# ASIC_1.net
KiCad netlist of a schematic drawn in Altium Designer
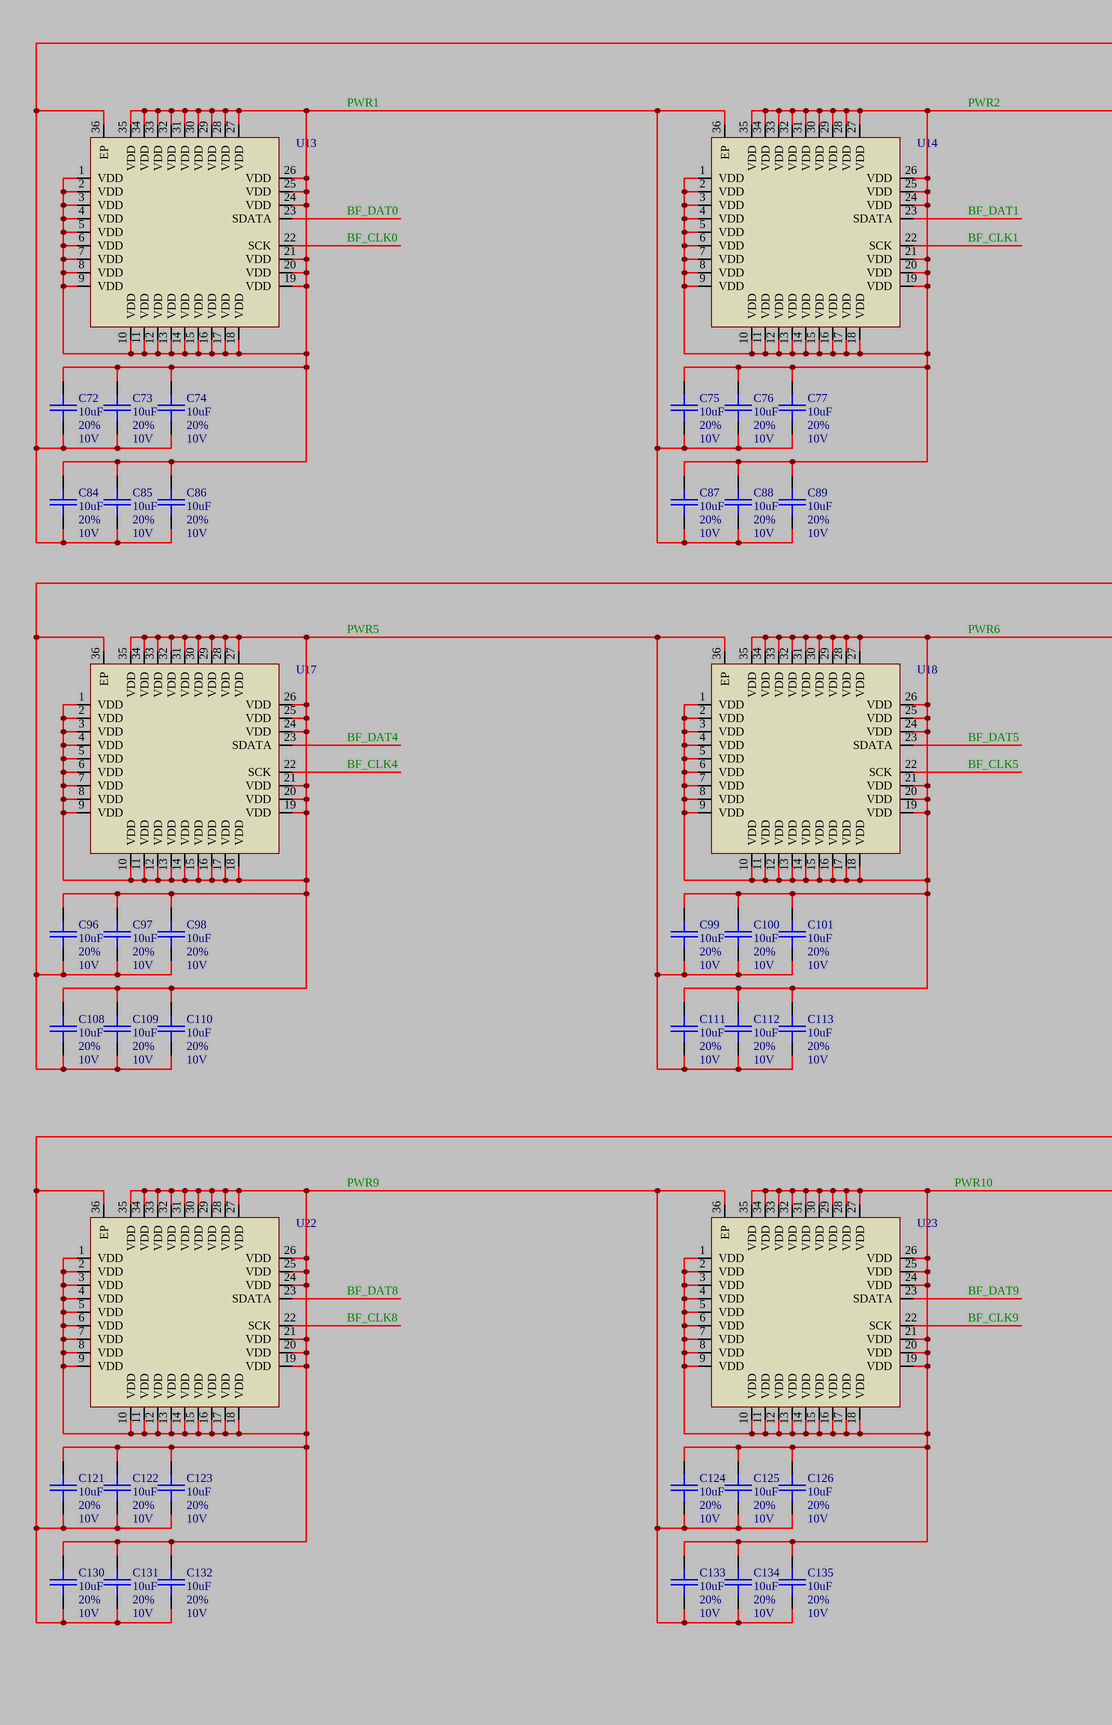
[diagram p0: ASIC_1.SchDoc, left]
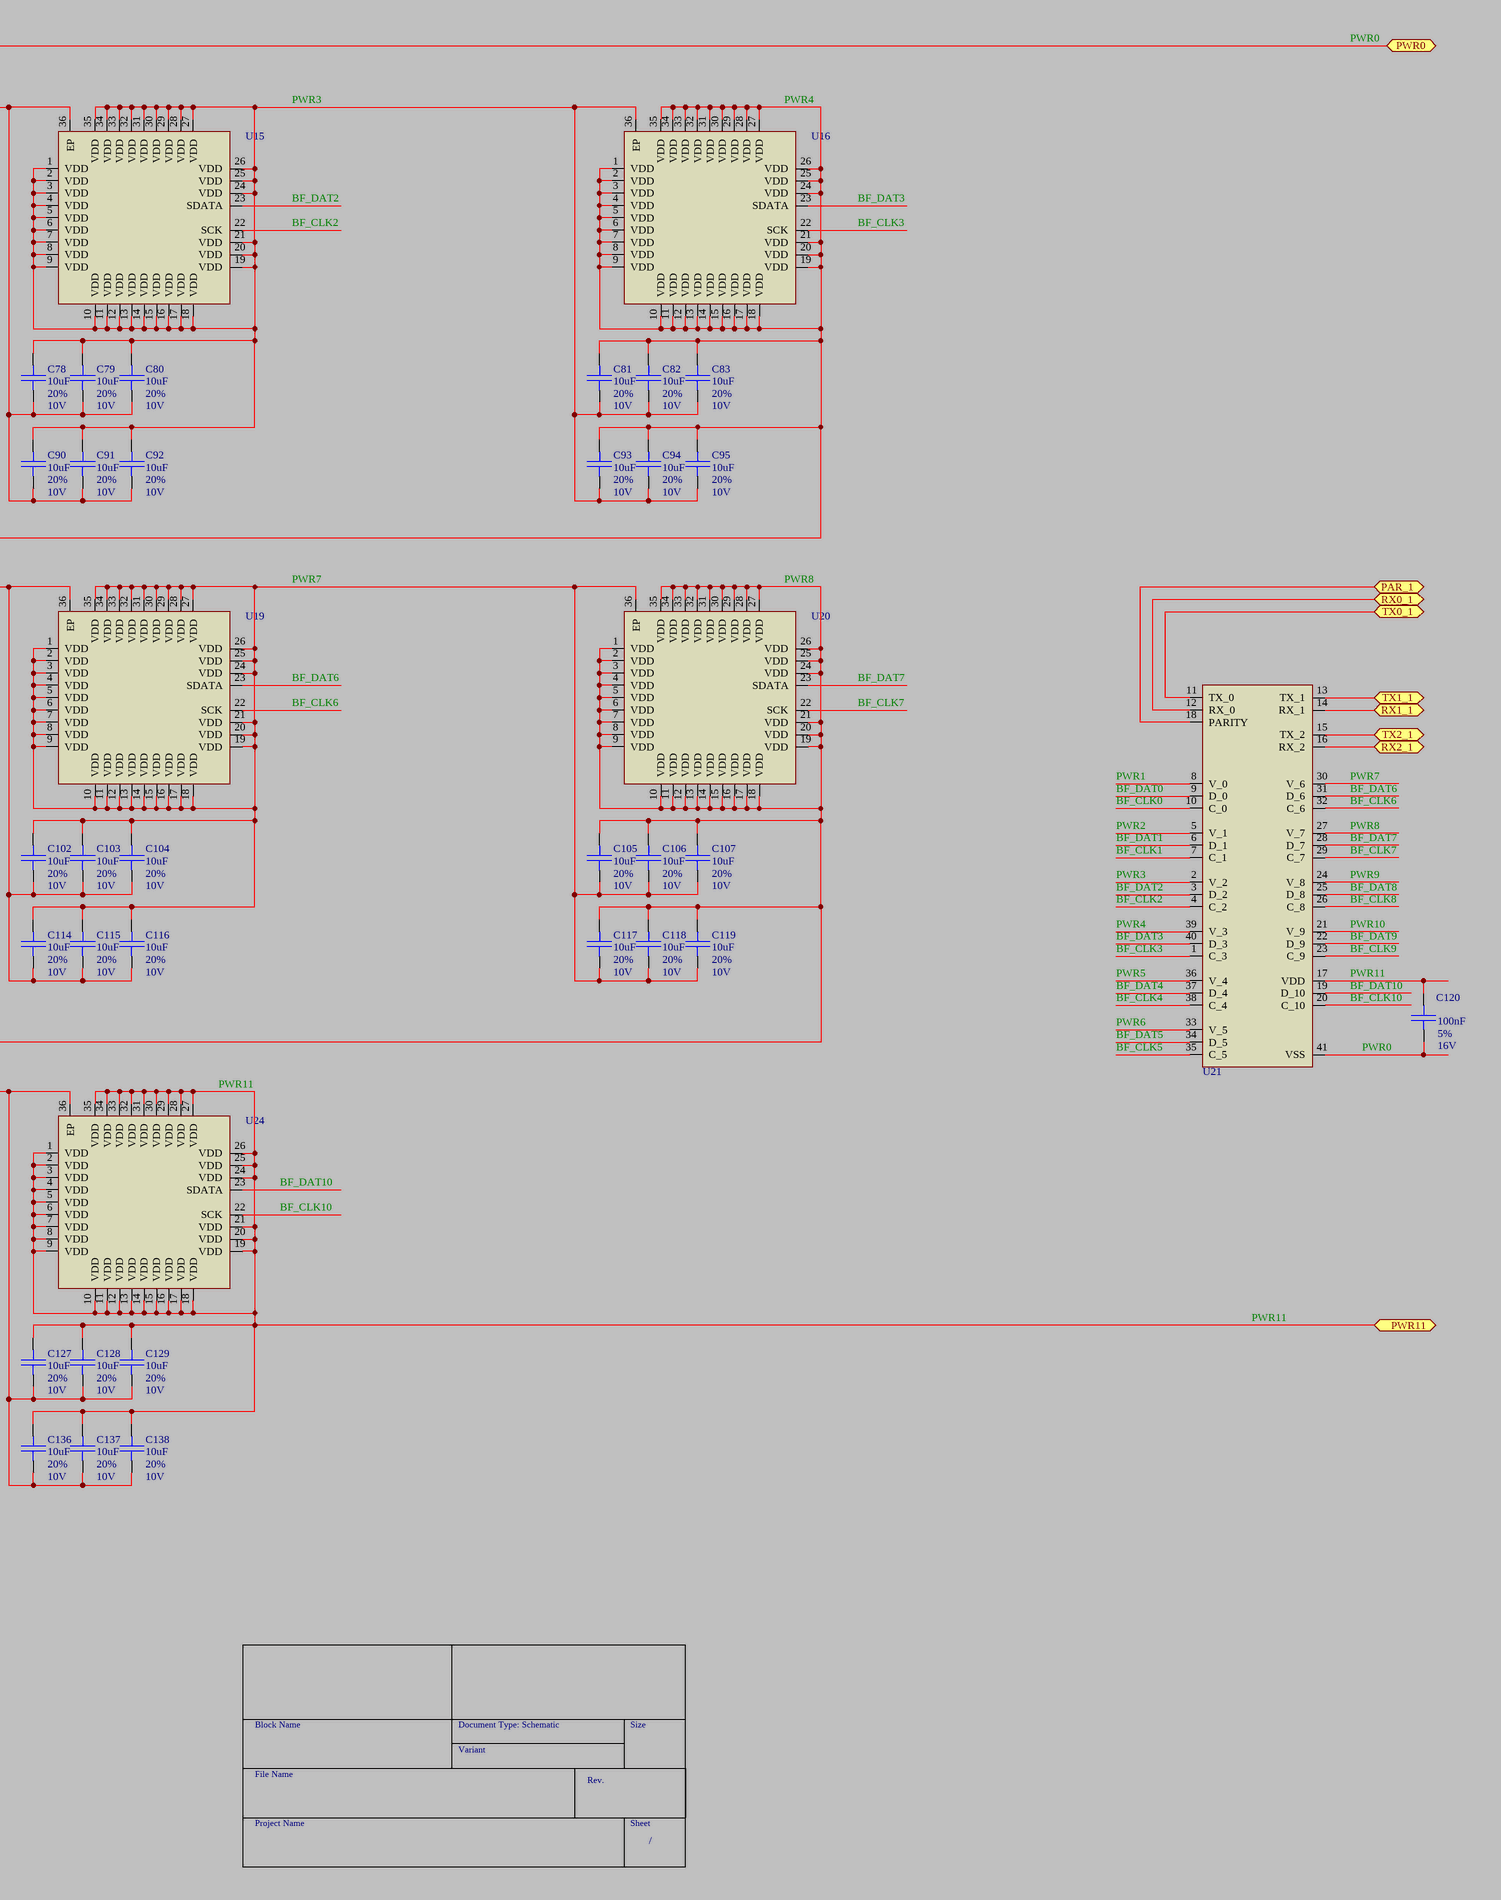
[diagram p1: ASIC_1.SchDoc, right]

(export (version "E")
  (design (tool "Eeschema 10.0.6"))
  (components
    (comp (ref "C72")
      (value "C")
      (footprint "SMD_0402_CAPC1005X70N")
      (fields
        (field (name "DB_PART_NUMBER") "CAP000047481")
        (field (name "DB_VALUE") "10uF")
        (field (name "DB_TOLERANCE") "20%")
        (field (name "DB_VOLTAGE") "10V")
        (field (name "DB_MANUFACTURER_PART") "SAMSUNG    CL05A106MP5NUNC")
        (field (name "DB_APPROVED_BY") "VSN")
      )
      (libsource (lib "Database_Libs1") (part "C"))
    )
    (comp (ref "C73")
      (value "C")
      (footprint "SMD_0402_CAPC1005X70N")
      (fields
        (field (name "DB_PART_NUMBER") "CAP000047481")
        (field (name "DB_VALUE") "10uF")
        (field (name "DB_TOLERANCE") "20%")
        (field (name "DB_VOLTAGE") "10V")
        (field (name "DB_MANUFACTURER_PART") "SAMSUNG    CL05A106MP5NUNC")
        (field (name "DB_APPROVED_BY") "VSN")
      )
      (libsource (lib "Database_Libs1") (part "C"))
    )
    (comp (ref "C74")
      (value "C")
      (footprint "SMD_0402_CAPC1005X70N")
      (fields
        (field (name "DB_PART_NUMBER") "CAP000047481")
        (field (name "DB_VALUE") "10uF")
        (field (name "DB_TOLERANCE") "20%")
        (field (name "DB_VOLTAGE") "10V")
        (field (name "DB_MANUFACTURER_PART") "SAMSUNG    CL05A106MP5NUNC")
        (field (name "DB_APPROVED_BY") "VSN")
      )
      (libsource (lib "Database_Libs1") (part "C"))
    )
    (comp (ref "C75")
      (value "C")
      (footprint "SMD_0402_CAPC1005X70N")
      (fields
        (field (name "DB_PART_NUMBER") "CAP000047481")
        (field (name "DB_VALUE") "10uF")
        (field (name "DB_TOLERANCE") "20%")
        (field (name "DB_VOLTAGE") "10V")
        (field (name "DB_MANUFACTURER_PART") "SAMSUNG    CL05A106MP5NUNC")
        (field (name "DB_APPROVED_BY") "VSN")
      )
      (libsource (lib "Database_Libs1") (part "C"))
    )
    (comp (ref "C76")
      (value "C")
      (footprint "SMD_0402_CAPC1005X70N")
      (fields
        (field (name "DB_PART_NUMBER") "CAP000047481")
        (field (name "DB_VALUE") "10uF")
        (field (name "DB_TOLERANCE") "20%")
        (field (name "DB_VOLTAGE") "10V")
        (field (name "DB_MANUFACTURER_PART") "SAMSUNG    CL05A106MP5NUNC")
        (field (name "DB_APPROVED_BY") "VSN")
      )
      (libsource (lib "Database_Libs1") (part "C"))
    )
    (comp (ref "C77")
      (value "C")
      (footprint "SMD_0402_CAPC1005X70N")
      (fields
        (field (name "DB_PART_NUMBER") "CAP000047481")
        (field (name "DB_VALUE") "10uF")
        (field (name "DB_TOLERANCE") "20%")
        (field (name "DB_VOLTAGE") "10V")
        (field (name "DB_MANUFACTURER_PART") "SAMSUNG    CL05A106MP5NUNC")
        (field (name "DB_APPROVED_BY") "VSN")
      )
      (libsource (lib "Database_Libs1") (part "C"))
    )
    (comp (ref "C78")
      (value "C")
      (footprint "SMD_0402_CAPC1005X70N")
      (fields
        (field (name "DB_PART_NUMBER") "CAP000047481")
        (field (name "DB_VALUE") "10uF")
        (field (name "DB_TOLERANCE") "20%")
        (field (name "DB_VOLTAGE") "10V")
        (field (name "DB_MANUFACTURER_PART") "SAMSUNG    CL05A106MP5NUNC")
        (field (name "DB_APPROVED_BY") "VSN")
      )
      (libsource (lib "Database_Libs1") (part "C"))
    )
    (comp (ref "C79")
      (value "C")
      (footprint "SMD_0402_CAPC1005X70N")
      (fields
        (field (name "DB_PART_NUMBER") "CAP000047481")
        (field (name "DB_VALUE") "10uF")
        (field (name "DB_TOLERANCE") "20%")
        (field (name "DB_VOLTAGE") "10V")
        (field (name "DB_MANUFACTURER_PART") "SAMSUNG    CL05A106MP5NUNC")
        (field (name "DB_APPROVED_BY") "VSN")
      )
      (libsource (lib "Database_Libs1") (part "C"))
    )
    (comp (ref "C80")
      (value "C")
      (footprint "SMD_0402_CAPC1005X70N")
      (fields
        (field (name "DB_PART_NUMBER") "CAP000047481")
        (field (name "DB_VALUE") "10uF")
        (field (name "DB_TOLERANCE") "20%")
        (field (name "DB_VOLTAGE") "10V")
        (field (name "DB_MANUFACTURER_PART") "SAMSUNG    CL05A106MP5NUNC")
        (field (name "DB_APPROVED_BY") "VSN")
      )
      (libsource (lib "Database_Libs1") (part "C"))
    )
    (comp (ref "C81")
      (value "C")
      (footprint "SMD_0402_CAPC1005X70N")
      (fields
        (field (name "DB_PART_NUMBER") "CAP000047481")
        (field (name "DB_VALUE") "10uF")
        (field (name "DB_TOLERANCE") "20%")
        (field (name "DB_VOLTAGE") "10V")
        (field (name "DB_MANUFACTURER_PART") "SAMSUNG    CL05A106MP5NUNC")
        (field (name "DB_APPROVED_BY") "VSN")
      )
      (libsource (lib "Database_Libs1") (part "C"))
    )
    (comp (ref "C82")
      (value "C")
      (footprint "SMD_0402_CAPC1005X70N")
      (fields
        (field (name "DB_PART_NUMBER") "CAP000047481")
        (field (name "DB_VALUE") "10uF")
        (field (name "DB_TOLERANCE") "20%")
        (field (name "DB_VOLTAGE") "10V")
        (field (name "DB_MANUFACTURER_PART") "SAMSUNG    CL05A106MP5NUNC")
        (field (name "DB_APPROVED_BY") "VSN")
      )
      (libsource (lib "Database_Libs1") (part "C"))
    )
    (comp (ref "C83")
      (value "C")
      (footprint "SMD_0402_CAPC1005X70N")
      (fields
        (field (name "DB_PART_NUMBER") "CAP000047481")
        (field (name "DB_VALUE") "10uF")
        (field (name "DB_TOLERANCE") "20%")
        (field (name "DB_VOLTAGE") "10V")
        (field (name "DB_MANUFACTURER_PART") "SAMSUNG    CL05A106MP5NUNC")
        (field (name "DB_APPROVED_BY") "VSN")
      )
      (libsource (lib "Database_Libs1") (part "C"))
    )
    (comp (ref "C84")
      (value "C")
      (footprint "SMD_0402_CAPC1005X70N")
      (fields
        (field (name "DB_PART_NUMBER") "CAP000047481")
        (field (name "DB_VALUE") "10uF")
        (field (name "DB_TOLERANCE") "20%")
        (field (name "DB_VOLTAGE") "10V")
        (field (name "DB_MANUFACTURER_PART") "SAMSUNG    CL05A106MP5NUNC")
        (field (name "DB_APPROVED_BY") "VSN")
      )
      (libsource (lib "Database_Libs1") (part "C"))
    )
    (comp (ref "C85")
      (value "C")
      (footprint "SMD_0402_CAPC1005X70N")
      (fields
        (field (name "DB_PART_NUMBER") "CAP000047481")
        (field (name "DB_VALUE") "10uF")
        (field (name "DB_TOLERANCE") "20%")
        (field (name "DB_VOLTAGE") "10V")
        (field (name "DB_MANUFACTURER_PART") "SAMSUNG    CL05A106MP5NUNC")
        (field (name "DB_APPROVED_BY") "VSN")
      )
      (libsource (lib "Database_Libs1") (part "C"))
    )
    (comp (ref "C86")
      (value "C")
      (footprint "SMD_0402_CAPC1005X70N")
      (fields
        (field (name "DB_PART_NUMBER") "CAP000047481")
        (field (name "DB_VALUE") "10uF")
        (field (name "DB_TOLERANCE") "20%")
        (field (name "DB_VOLTAGE") "10V")
        (field (name "DB_MANUFACTURER_PART") "SAMSUNG    CL05A106MP5NUNC")
        (field (name "DB_APPROVED_BY") "VSN")
      )
      (libsource (lib "Database_Libs1") (part "C"))
    )
    (comp (ref "C87")
      (value "C")
      (footprint "SMD_0402_CAPC1005X70N")
      (fields
        (field (name "DB_PART_NUMBER") "CAP000047481")
        (field (name "DB_VALUE") "10uF")
        (field (name "DB_TOLERANCE") "20%")
        (field (name "DB_VOLTAGE") "10V")
        (field (name "DB_MANUFACTURER_PART") "SAMSUNG    CL05A106MP5NUNC")
        (field (name "DB_APPROVED_BY") "VSN")
      )
      (libsource (lib "Database_Libs1") (part "C"))
    )
    (comp (ref "C88")
      (value "C")
      (footprint "SMD_0402_CAPC1005X70N")
      (fields
        (field (name "DB_PART_NUMBER") "CAP000047481")
        (field (name "DB_VALUE") "10uF")
        (field (name "DB_TOLERANCE") "20%")
        (field (name "DB_VOLTAGE") "10V")
        (field (name "DB_MANUFACTURER_PART") "SAMSUNG    CL05A106MP5NUNC")
        (field (name "DB_APPROVED_BY") "VSN")
      )
      (libsource (lib "Database_Libs1") (part "C"))
    )
    (comp (ref "C89")
      (value "C")
      (footprint "SMD_0402_CAPC1005X70N")
      (fields
        (field (name "DB_PART_NUMBER") "CAP000047481")
        (field (name "DB_VALUE") "10uF")
        (field (name "DB_TOLERANCE") "20%")
        (field (name "DB_VOLTAGE") "10V")
        (field (name "DB_MANUFACTURER_PART") "SAMSUNG    CL05A106MP5NUNC")
        (field (name "DB_APPROVED_BY") "VSN")
      )
      (libsource (lib "Database_Libs1") (part "C"))
    )
    (comp (ref "C90")
      (value "C")
      (footprint "SMD_0402_CAPC1005X70N")
      (fields
        (field (name "DB_PART_NUMBER") "CAP000047481")
        (field (name "DB_VALUE") "10uF")
        (field (name "DB_TOLERANCE") "20%")
        (field (name "DB_VOLTAGE") "10V")
        (field (name "DB_MANUFACTURER_PART") "SAMSUNG    CL05A106MP5NUNC")
        (field (name "DB_APPROVED_BY") "VSN")
      )
      (libsource (lib "Database_Libs1") (part "C"))
    )
    (comp (ref "C91")
      (value "C")
      (footprint "SMD_0402_CAPC1005X70N")
      (fields
        (field (name "DB_PART_NUMBER") "CAP000047481")
        (field (name "DB_VALUE") "10uF")
        (field (name "DB_TOLERANCE") "20%")
        (field (name "DB_VOLTAGE") "10V")
        (field (name "DB_MANUFACTURER_PART") "SAMSUNG    CL05A106MP5NUNC")
        (field (name "DB_APPROVED_BY") "VSN")
      )
      (libsource (lib "Database_Libs1") (part "C"))
    )
    (comp (ref "C92")
      (value "C")
      (footprint "SMD_0402_CAPC1005X70N")
      (fields
        (field (name "DB_PART_NUMBER") "CAP000047481")
        (field (name "DB_VALUE") "10uF")
        (field (name "DB_TOLERANCE") "20%")
        (field (name "DB_VOLTAGE") "10V")
        (field (name "DB_MANUFACTURER_PART") "SAMSUNG    CL05A106MP5NUNC")
        (field (name "DB_APPROVED_BY") "VSN")
      )
      (libsource (lib "Database_Libs1") (part "C"))
    )
    (comp (ref "C93")
      (value "C")
      (footprint "SMD_0402_CAPC1005X70N")
      (fields
        (field (name "DB_PART_NUMBER") "CAP000047481")
        (field (name "DB_VALUE") "10uF")
        (field (name "DB_TOLERANCE") "20%")
        (field (name "DB_VOLTAGE") "10V")
        (field (name "DB_MANUFACTURER_PART") "SAMSUNG    CL05A106MP5NUNC")
        (field (name "DB_APPROVED_BY") "VSN")
      )
      (libsource (lib "Database_Libs1") (part "C"))
    )
    (comp (ref "C94")
      (value "C")
      (footprint "SMD_0402_CAPC1005X70N")
      (fields
        (field (name "DB_PART_NUMBER") "CAP000047481")
        (field (name "DB_VALUE") "10uF")
        (field (name "DB_TOLERANCE") "20%")
        (field (name "DB_VOLTAGE") "10V")
        (field (name "DB_MANUFACTURER_PART") "SAMSUNG    CL05A106MP5NUNC")
        (field (name "DB_APPROVED_BY") "VSN")
      )
      (libsource (lib "Database_Libs1") (part "C"))
    )
    (comp (ref "C95")
      (value "C")
      (footprint "SMD_0402_CAPC1005X70N")
      (fields
        (field (name "DB_PART_NUMBER") "CAP000047481")
        (field (name "DB_VALUE") "10uF")
        (field (name "DB_TOLERANCE") "20%")
        (field (name "DB_VOLTAGE") "10V")
        (field (name "DB_MANUFACTURER_PART") "SAMSUNG    CL05A106MP5NUNC")
        (field (name "DB_APPROVED_BY") "VSN")
      )
      (libsource (lib "Database_Libs1") (part "C"))
    )
    (comp (ref "C96")
      (value "C")
      (footprint "SMD_0402_CAPC1005X70N")
      (fields
        (field (name "DB_PART_NUMBER") "CAP000047481")
        (field (name "DB_VALUE") "10uF")
        (field (name "DB_TOLERANCE") "20%")
        (field (name "DB_VOLTAGE") "10V")
        (field (name "DB_MANUFACTURER_PART") "SAMSUNG    CL05A106MP5NUNC")
        (field (name "DB_APPROVED_BY") "VSN")
      )
      (libsource (lib "Database_Libs1") (part "C"))
    )
    (comp (ref "C97")
      (value "C")
      (footprint "SMD_0402_CAPC1005X70N")
      (fields
        (field (name "DB_PART_NUMBER") "CAP000047481")
        (field (name "DB_VALUE") "10uF")
        (field (name "DB_TOLERANCE") "20%")
        (field (name "DB_VOLTAGE") "10V")
        (field (name "DB_MANUFACTURER_PART") "SAMSUNG    CL05A106MP5NUNC")
        (field (name "DB_APPROVED_BY") "VSN")
      )
      (libsource (lib "Database_Libs1") (part "C"))
    )
    (comp (ref "C98")
      (value "C")
      (footprint "SMD_0402_CAPC1005X70N")
      (fields
        (field (name "DB_PART_NUMBER") "CAP000047481")
        (field (name "DB_VALUE") "10uF")
        (field (name "DB_TOLERANCE") "20%")
        (field (name "DB_VOLTAGE") "10V")
        (field (name "DB_MANUFACTURER_PART") "SAMSUNG    CL05A106MP5NUNC")
        (field (name "DB_APPROVED_BY") "VSN")
      )
      (libsource (lib "Database_Libs1") (part "C"))
    )
    (comp (ref "C99")
      (value "C")
      (footprint "SMD_0402_CAPC1005X70N")
      (fields
        (field (name "DB_PART_NUMBER") "CAP000047481")
        (field (name "DB_VALUE") "10uF")
        (field (name "DB_TOLERANCE") "20%")
        (field (name "DB_VOLTAGE") "10V")
        (field (name "DB_MANUFACTURER_PART") "SAMSUNG    CL05A106MP5NUNC")
        (field (name "DB_APPROVED_BY") "VSN")
      )
      (libsource (lib "Database_Libs1") (part "C"))
    )
    (comp (ref "C100")
      (value "C")
      (footprint "SMD_0402_CAPC1005X70N")
      (fields
        (field (name "DB_PART_NUMBER") "CAP000047481")
        (field (name "DB_VALUE") "10uF")
        (field (name "DB_TOLERANCE") "20%")
        (field (name "DB_VOLTAGE") "10V")
        (field (name "DB_MANUFACTURER_PART") "SAMSUNG    CL05A106MP5NUNC")
        (field (name "DB_APPROVED_BY") "VSN")
      )
      (libsource (lib "Database_Libs1") (part "C"))
    )
    (comp (ref "C101")
      (value "C")
      (footprint "SMD_0402_CAPC1005X70N")
      (fields
        (field (name "DB_PART_NUMBER") "CAP000047481")
        (field (name "DB_VALUE") "10uF")
        (field (name "DB_TOLERANCE") "20%")
        (field (name "DB_VOLTAGE") "10V")
        (field (name "DB_MANUFACTURER_PART") "SAMSUNG    CL05A106MP5NUNC")
        (field (name "DB_APPROVED_BY") "VSN")
      )
      (libsource (lib "Database_Libs1") (part "C"))
    )
    (comp (ref "C102")
      (value "C")
      (footprint "SMD_0402_CAPC1005X70N")
      (fields
        (field (name "DB_PART_NUMBER") "CAP000047481")
        (field (name "DB_VALUE") "10uF")
        (field (name "DB_TOLERANCE") "20%")
        (field (name "DB_VOLTAGE") "10V")
        (field (name "DB_MANUFACTURER_PART") "SAMSUNG    CL05A106MP5NUNC")
        (field (name "DB_APPROVED_BY") "VSN")
      )
      (libsource (lib "Database_Libs1") (part "C"))
    )
    (comp (ref "C103")
      (value "C")
      (footprint "SMD_0402_CAPC1005X70N")
      (fields
        (field (name "DB_PART_NUMBER") "CAP000047481")
        (field (name "DB_VALUE") "10uF")
        (field (name "DB_TOLERANCE") "20%")
        (field (name "DB_VOLTAGE") "10V")
        (field (name "DB_MANUFACTURER_PART") "SAMSUNG    CL05A106MP5NUNC")
        (field (name "DB_APPROVED_BY") "VSN")
      )
      (libsource (lib "Database_Libs1") (part "C"))
    )
    (comp (ref "C104")
      (value "C")
      (footprint "SMD_0402_CAPC1005X70N")
      (fields
        (field (name "DB_PART_NUMBER") "CAP000047481")
        (field (name "DB_VALUE") "10uF")
        (field (name "DB_TOLERANCE") "20%")
        (field (name "DB_VOLTAGE") "10V")
        (field (name "DB_MANUFACTURER_PART") "SAMSUNG    CL05A106MP5NUNC")
        (field (name "DB_APPROVED_BY") "VSN")
      )
      (libsource (lib "Database_Libs1") (part "C"))
    )
    (comp (ref "C105")
      (value "C")
      (footprint "SMD_0402_CAPC1005X70N")
      (fields
        (field (name "DB_PART_NUMBER") "CAP000047481")
        (field (name "DB_VALUE") "10uF")
        (field (name "DB_TOLERANCE") "20%")
        (field (name "DB_VOLTAGE") "10V")
        (field (name "DB_MANUFACTURER_PART") "SAMSUNG    CL05A106MP5NUNC")
        (field (name "DB_APPROVED_BY") "VSN")
      )
      (libsource (lib "Database_Libs1") (part "C"))
    )
    (comp (ref "C106")
      (value "C")
      (footprint "SMD_0402_CAPC1005X70N")
      (fields
        (field (name "DB_PART_NUMBER") "CAP000047481")
        (field (name "DB_VALUE") "10uF")
        (field (name "DB_TOLERANCE") "20%")
        (field (name "DB_VOLTAGE") "10V")
        (field (name "DB_MANUFACTURER_PART") "SAMSUNG    CL05A106MP5NUNC")
        (field (name "DB_APPROVED_BY") "VSN")
      )
      (libsource (lib "Database_Libs1") (part "C"))
    )
    (comp (ref "C107")
      (value "C")
      (footprint "SMD_0402_CAPC1005X70N")
      (fields
        (field (name "DB_PART_NUMBER") "CAP000047481")
        (field (name "DB_VALUE") "10uF")
        (field (name "DB_TOLERANCE") "20%")
        (field (name "DB_VOLTAGE") "10V")
        (field (name "DB_MANUFACTURER_PART") "SAMSUNG    CL05A106MP5NUNC")
        (field (name "DB_APPROVED_BY") "VSN")
      )
      (libsource (lib "Database_Libs1") (part "C"))
    )
    (comp (ref "C108")
      (value "C")
      (footprint "SMD_0402_CAPC1005X70N")
      (fields
        (field (name "DB_PART_NUMBER") "CAP000047481")
        (field (name "DB_VALUE") "10uF")
        (field (name "DB_TOLERANCE") "20%")
        (field (name "DB_VOLTAGE") "10V")
        (field (name "DB_MANUFACTURER_PART") "SAMSUNG    CL05A106MP5NUNC")
        (field (name "DB_APPROVED_BY") "VSN")
      )
      (libsource (lib "Database_Libs1") (part "C"))
    )
    (comp (ref "C109")
      (value "C")
      (footprint "SMD_0402_CAPC1005X70N")
      (fields
        (field (name "DB_PART_NUMBER") "CAP000047481")
        (field (name "DB_VALUE") "10uF")
        (field (name "DB_TOLERANCE") "20%")
        (field (name "DB_VOLTAGE") "10V")
        (field (name "DB_MANUFACTURER_PART") "SAMSUNG    CL05A106MP5NUNC")
        (field (name "DB_APPROVED_BY") "VSN")
      )
      (libsource (lib "Database_Libs1") (part "C"))
    )
    (comp (ref "C110")
      (value "C")
      (footprint "SMD_0402_CAPC1005X70N")
      (fields
        (field (name "DB_PART_NUMBER") "CAP000047481")
        (field (name "DB_VALUE") "10uF")
        (field (name "DB_TOLERANCE") "20%")
        (field (name "DB_VOLTAGE") "10V")
        (field (name "DB_MANUFACTURER_PART") "SAMSUNG    CL05A106MP5NUNC")
        (field (name "DB_APPROVED_BY") "VSN")
      )
      (libsource (lib "Database_Libs1") (part "C"))
    )
    (comp (ref "C111")
      (value "C")
      (footprint "SMD_0402_CAPC1005X70N")
      (fields
        (field (name "DB_PART_NUMBER") "CAP000047481")
        (field (name "DB_VALUE") "10uF")
        (field (name "DB_TOLERANCE") "20%")
        (field (name "DB_VOLTAGE") "10V")
        (field (name "DB_MANUFACTURER_PART") "SAMSUNG    CL05A106MP5NUNC")
        (field (name "DB_APPROVED_BY") "VSN")
      )
      (libsource (lib "Database_Libs1") (part "C"))
    )
    (comp (ref "C112")
      (value "C")
      (footprint "SMD_0402_CAPC1005X70N")
      (fields
        (field (name "DB_PART_NUMBER") "CAP000047481")
        (field (name "DB_VALUE") "10uF")
        (field (name "DB_TOLERANCE") "20%")
        (field (name "DB_VOLTAGE") "10V")
        (field (name "DB_MANUFACTURER_PART") "SAMSUNG    CL05A106MP5NUNC")
        (field (name "DB_APPROVED_BY") "VSN")
      )
      (libsource (lib "Database_Libs1") (part "C"))
    )
    (comp (ref "C113")
      (value "C")
      (footprint "SMD_0402_CAPC1005X70N")
      (fields
        (field (name "DB_PART_NUMBER") "CAP000047481")
        (field (name "DB_VALUE") "10uF")
        (field (name "DB_TOLERANCE") "20%")
        (field (name "DB_VOLTAGE") "10V")
        (field (name "DB_MANUFACTURER_PART") "SAMSUNG    CL05A106MP5NUNC")
        (field (name "DB_APPROVED_BY") "VSN")
      )
      (libsource (lib "Database_Libs1") (part "C"))
    )
    (comp (ref "C114")
      (value "C")
      (footprint "SMD_0402_CAPC1005X70N")
      (fields
        (field (name "DB_PART_NUMBER") "CAP000047481")
        (field (name "DB_VALUE") "10uF")
        (field (name "DB_TOLERANCE") "20%")
        (field (name "DB_VOLTAGE") "10V")
        (field (name "DB_MANUFACTURER_PART") "SAMSUNG    CL05A106MP5NUNC")
        (field (name "DB_APPROVED_BY") "VSN")
      )
      (libsource (lib "Database_Libs1") (part "C"))
    )
    (comp (ref "C115")
      (value "C")
      (footprint "SMD_0402_CAPC1005X70N")
      (fields
        (field (name "DB_PART_NUMBER") "CAP000047481")
        (field (name "DB_VALUE") "10uF")
        (field (name "DB_TOLERANCE") "20%")
        (field (name "DB_VOLTAGE") "10V")
        (field (name "DB_MANUFACTURER_PART") "SAMSUNG    CL05A106MP5NUNC")
        (field (name "DB_APPROVED_BY") "VSN")
      )
      (libsource (lib "Database_Libs1") (part "C"))
    )
    (comp (ref "C116")
      (value "C")
      (footprint "SMD_0402_CAPC1005X70N")
      (fields
        (field (name "DB_PART_NUMBER") "CAP000047481")
        (field (name "DB_VALUE") "10uF")
        (field (name "DB_TOLERANCE") "20%")
        (field (name "DB_VOLTAGE") "10V")
        (field (name "DB_MANUFACTURER_PART") "SAMSUNG    CL05A106MP5NUNC")
        (field (name "DB_APPROVED_BY") "VSN")
      )
      (libsource (lib "Database_Libs1") (part "C"))
    )
    (comp (ref "C117")
      (value "C")
      (footprint "SMD_0402_CAPC1005X70N")
      (fields
        (field (name "DB_PART_NUMBER") "CAP000047481")
        (field (name "DB_VALUE") "10uF")
        (field (name "DB_TOLERANCE") "20%")
        (field (name "DB_VOLTAGE") "10V")
        (field (name "DB_MANUFACTURER_PART") "SAMSUNG    CL05A106MP5NUNC")
        (field (name "DB_APPROVED_BY") "VSN")
      )
      (libsource (lib "Database_Libs1") (part "C"))
    )
    (comp (ref "C118")
      (value "C")
      (footprint "SMD_0402_CAPC1005X70N")
      (fields
        (field (name "DB_PART_NUMBER") "CAP000047481")
        (field (name "DB_VALUE") "10uF")
        (field (name "DB_TOLERANCE") "20%")
        (field (name "DB_VOLTAGE") "10V")
        (field (name "DB_MANUFACTURER_PART") "SAMSUNG    CL05A106MP5NUNC")
        (field (name "DB_APPROVED_BY") "VSN")
      )
      (libsource (lib "Database_Libs1") (part "C"))
    )
    (comp (ref "C119")
      (value "C")
      (footprint "SMD_0402_CAPC1005X70N")
      (fields
        (field (name "DB_PART_NUMBER") "CAP000047481")
        (field (name "DB_VALUE") "10uF")
        (field (name "DB_TOLERANCE") "20%")
        (field (name "DB_VOLTAGE") "10V")
        (field (name "DB_MANUFACTURER_PART") "SAMSUNG    CL05A106MP5NUNC")
        (field (name "DB_APPROVED_BY") "VSN")
      )
      (libsource (lib "Database_Libs1") (part "C"))
    )
    (comp (ref "C120")
      (value "C")
      (footprint "SMD_0603_CAPC1608X95N")
      (fields
        (field (name "DB_PART_NUMBER") "CAP000027134")
        (field (name "DB_VALUE") "100nF")
        (field (name "DB_TOLERANCE") "5%")
        (field (name "DB_VOLTAGE") "16V")
        (field (name "DB_MANUFACTURER_PART") "KEMET    C0603C104J4RAC")
      )
      (libsource (lib "Database_Libs1") (part "C"))
    )
    (comp (ref "C121")
      (value "C")
      (footprint "SMD_0402_CAPC1005X70N")
      (fields
        (field (name "DB_PART_NUMBER") "CAP000047481")
        (field (name "DB_VALUE") "10uF")
        (field (name "DB_TOLERANCE") "20%")
        (field (name "DB_VOLTAGE") "10V")
        (field (name "DB_MANUFACTURER_PART") "SAMSUNG    CL05A106MP5NUNC")
        (field (name "DB_APPROVED_BY") "VSN")
      )
      (libsource (lib "Database_Libs1") (part "C"))
    )
    (comp (ref "C122")
      (value "C")
      (footprint "SMD_0402_CAPC1005X70N")
      (fields
        (field (name "DB_PART_NUMBER") "CAP000047481")
        (field (name "DB_VALUE") "10uF")
        (field (name "DB_TOLERANCE") "20%")
        (field (name "DB_VOLTAGE") "10V")
        (field (name "DB_MANUFACTURER_PART") "SAMSUNG    CL05A106MP5NUNC")
        (field (name "DB_APPROVED_BY") "VSN")
      )
      (libsource (lib "Database_Libs1") (part "C"))
    )
    (comp (ref "C123")
      (value "C")
      (footprint "SMD_0402_CAPC1005X70N")
      (fields
        (field (name "DB_PART_NUMBER") "CAP000047481")
        (field (name "DB_VALUE") "10uF")
        (field (name "DB_TOLERANCE") "20%")
        (field (name "DB_VOLTAGE") "10V")
        (field (name "DB_MANUFACTURER_PART") "SAMSUNG    CL05A106MP5NUNC")
        (field (name "DB_APPROVED_BY") "VSN")
      )
      (libsource (lib "Database_Libs1") (part "C"))
    )
    (comp (ref "C124")
      (value "C")
      (footprint "SMD_0402_CAPC1005X70N")
      (fields
        (field (name "DB_PART_NUMBER") "CAP000047481")
        (field (name "DB_VALUE") "10uF")
        (field (name "DB_TOLERANCE") "20%")
        (field (name "DB_VOLTAGE") "10V")
        (field (name "DB_MANUFACTURER_PART") "SAMSUNG    CL05A106MP5NUNC")
        (field (name "DB_APPROVED_BY") "VSN")
      )
      (libsource (lib "Database_Libs1") (part "C"))
    )
    (comp (ref "C125")
      (value "C")
      (footprint "SMD_0402_CAPC1005X70N")
      (fields
        (field (name "DB_PART_NUMBER") "CAP000047481")
        (field (name "DB_VALUE") "10uF")
        (field (name "DB_TOLERANCE") "20%")
        (field (name "DB_VOLTAGE") "10V")
        (field (name "DB_MANUFACTURER_PART") "SAMSUNG    CL05A106MP5NUNC")
        (field (name "DB_APPROVED_BY") "VSN")
      )
      (libsource (lib "Database_Libs1") (part "C"))
    )
    (comp (ref "C126")
      (value "C")
      (footprint "SMD_0402_CAPC1005X70N")
      (fields
        (field (name "DB_PART_NUMBER") "CAP000047481")
        (field (name "DB_VALUE") "10uF")
        (field (name "DB_TOLERANCE") "20%")
        (field (name "DB_VOLTAGE") "10V")
        (field (name "DB_MANUFACTURER_PART") "SAMSUNG    CL05A106MP5NUNC")
        (field (name "DB_APPROVED_BY") "VSN")
      )
      (libsource (lib "Database_Libs1") (part "C"))
    )
    (comp (ref "C127")
      (value "C")
      (footprint "SMD_0402_CAPC1005X70N")
      (fields
        (field (name "DB_PART_NUMBER") "CAP000047481")
        (field (name "DB_VALUE") "10uF")
        (field (name "DB_TOLERANCE") "20%")
        (field (name "DB_VOLTAGE") "10V")
        (field (name "DB_MANUFACTURER_PART") "SAMSUNG    CL05A106MP5NUNC")
        (field (name "DB_APPROVED_BY") "VSN")
      )
      (libsource (lib "Database_Libs1") (part "C"))
    )
    (comp (ref "C128")
      (value "C")
      (footprint "SMD_0402_CAPC1005X70N")
      (fields
        (field (name "DB_PART_NUMBER") "CAP000047481")
        (field (name "DB_VALUE") "10uF")
        (field (name "DB_TOLERANCE") "20%")
        (field (name "DB_VOLTAGE") "10V")
        (field (name "DB_MANUFACTURER_PART") "SAMSUNG    CL05A106MP5NUNC")
        (field (name "DB_APPROVED_BY") "VSN")
      )
      (libsource (lib "Database_Libs1") (part "C"))
    )
    (comp (ref "C129")
      (value "C")
      (footprint "SMD_0402_CAPC1005X70N")
      (fields
        (field (name "DB_PART_NUMBER") "CAP000047481")
        (field (name "DB_VALUE") "10uF")
        (field (name "DB_TOLERANCE") "20%")
        (field (name "DB_VOLTAGE") "10V")
        (field (name "DB_MANUFACTURER_PART") "SAMSUNG    CL05A106MP5NUNC")
        (field (name "DB_APPROVED_BY") "VSN")
      )
      (libsource (lib "Database_Libs1") (part "C"))
    )
    (comp (ref "C130")
      (value "C")
      (footprint "SMD_0402_CAPC1005X70N")
      (fields
        (field (name "DB_PART_NUMBER") "CAP000047481")
        (field (name "DB_VALUE") "10uF")
        (field (name "DB_TOLERANCE") "20%")
        (field (name "DB_VOLTAGE") "10V")
        (field (name "DB_MANUFACTURER_PART") "SAMSUNG    CL05A106MP5NUNC")
        (field (name "DB_APPROVED_BY") "VSN")
      )
      (libsource (lib "Database_Libs1") (part "C"))
    )
    (comp (ref "C131")
      (value "C")
      (footprint "SMD_0402_CAPC1005X70N")
      (fields
        (field (name "DB_PART_NUMBER") "CAP000047481")
        (field (name "DB_VALUE") "10uF")
        (field (name "DB_TOLERANCE") "20%")
        (field (name "DB_VOLTAGE") "10V")
        (field (name "DB_MANUFACTURER_PART") "SAMSUNG    CL05A106MP5NUNC")
        (field (name "DB_APPROVED_BY") "VSN")
      )
      (libsource (lib "Database_Libs1") (part "C"))
    )
    (comp (ref "C132")
      (value "C")
      (footprint "SMD_0402_CAPC1005X70N")
      (fields
        (field (name "DB_PART_NUMBER") "CAP000047481")
        (field (name "DB_VALUE") "10uF")
        (field (name "DB_TOLERANCE") "20%")
        (field (name "DB_VOLTAGE") "10V")
        (field (name "DB_MANUFACTURER_PART") "SAMSUNG    CL05A106MP5NUNC")
        (field (name "DB_APPROVED_BY") "VSN")
      )
      (libsource (lib "Database_Libs1") (part "C"))
    )
    (comp (ref "C133")
      (value "C")
      (footprint "SMD_0402_CAPC1005X70N")
      (fields
        (field (name "DB_PART_NUMBER") "CAP000047481")
        (field (name "DB_VALUE") "10uF")
        (field (name "DB_TOLERANCE") "20%")
        (field (name "DB_VOLTAGE") "10V")
        (field (name "DB_MANUFACTURER_PART") "SAMSUNG    CL05A106MP5NUNC")
        (field (name "DB_APPROVED_BY") "VSN")
      )
      (libsource (lib "Database_Libs1") (part "C"))
    )
    (comp (ref "C134")
      (value "C")
      (footprint "SMD_0402_CAPC1005X70N")
      (fields
        (field (name "DB_PART_NUMBER") "CAP000047481")
        (field (name "DB_VALUE") "10uF")
        (field (name "DB_TOLERANCE") "20%")
        (field (name "DB_VOLTAGE") "10V")
        (field (name "DB_MANUFACTURER_PART") "SAMSUNG    CL05A106MP5NUNC")
        (field (name "DB_APPROVED_BY") "VSN")
      )
      (libsource (lib "Database_Libs1") (part "C"))
    )
    (comp (ref "C135")
      (value "C")
      (footprint "SMD_0402_CAPC1005X70N")
      (fields
        (field (name "DB_PART_NUMBER") "CAP000047481")
        (field (name "DB_VALUE") "10uF")
        (field (name "DB_TOLERANCE") "20%")
        (field (name "DB_VOLTAGE") "10V")
        (field (name "DB_MANUFACTURER_PART") "SAMSUNG    CL05A106MP5NUNC")
        (field (name "DB_APPROVED_BY") "VSN")
      )
      (libsource (lib "Database_Libs1") (part "C"))
    )
    (comp (ref "C136")
      (value "C")
      (footprint "SMD_0402_CAPC1005X70N")
      (fields
        (field (name "DB_PART_NUMBER") "CAP000047481")
        (field (name "DB_VALUE") "10uF")
        (field (name "DB_TOLERANCE") "20%")
        (field (name "DB_VOLTAGE") "10V")
        (field (name "DB_MANUFACTURER_PART") "SAMSUNG    CL05A106MP5NUNC")
        (field (name "DB_APPROVED_BY") "VSN")
      )
      (libsource (lib "Database_Libs1") (part "C"))
    )
    (comp (ref "C137")
      (value "C")
      (footprint "SMD_0402_CAPC1005X70N")
      (fields
        (field (name "DB_PART_NUMBER") "CAP000047481")
        (field (name "DB_VALUE") "10uF")
        (field (name "DB_TOLERANCE") "20%")
        (field (name "DB_VOLTAGE") "10V")
        (field (name "DB_MANUFACTURER_PART") "SAMSUNG    CL05A106MP5NUNC")
        (field (name "DB_APPROVED_BY") "VSN")
      )
      (libsource (lib "Database_Libs1") (part "C"))
    )
    (comp (ref "C138")
      (value "C")
      (footprint "SMD_0402_CAPC1005X70N")
      (fields
        (field (name "DB_PART_NUMBER") "CAP000047481")
        (field (name "DB_VALUE") "10uF")
        (field (name "DB_TOLERANCE") "20%")
        (field (name "DB_VOLTAGE") "10V")
        (field (name "DB_MANUFACTURER_PART") "SAMSUNG    CL05A106MP5NUNC")
        (field (name "DB_APPROVED_BY") "VSN")
      )
      (libsource (lib "Database_Libs1") (part "C"))
    )
    (comp (ref "U13")
      (value "IC_BITFURY16")
      (footprint "SMD_QFN50P600X600X175-36AN")
      (description "BitFury 2016 16 nm")
      (libsource (lib "BitCoin") (part "IC_BITFURY16"))
    )
    (comp (ref "U14")
      (value "IC_BITFURY16")
      (footprint "SMD_QFN50P600X600X175-36AN")
      (description "BitFury 2016 16 nm")
      (libsource (lib "BitCoin") (part "IC_BITFURY16"))
    )
    (comp (ref "U15")
      (value "IC_BITFURY16")
      (footprint "SMD_QFN50P600X600X175-36AN")
      (description "BitFury 2016 16 nm")
      (libsource (lib "BitCoin") (part "IC_BITFURY16"))
    )
    (comp (ref "U16")
      (value "IC_BITFURY16")
      (footprint "SMD_QFN50P600X600X175-36AN")
      (description "BitFury 2016 16 nm")
      (libsource (lib "BitCoin") (part "IC_BITFURY16"))
    )
    (comp (ref "U17")
      (value "IC_BITFURY16")
      (footprint "SMD_QFN50P600X600X175-36AN")
      (description "BitFury 2016 16 nm")
      (libsource (lib "BitCoin") (part "IC_BITFURY16"))
    )
    (comp (ref "U18")
      (value "IC_BITFURY16")
      (footprint "SMD_QFN50P600X600X175-36AN")
      (description "BitFury 2016 16 nm")
      (libsource (lib "BitCoin") (part "IC_BITFURY16"))
    )
    (comp (ref "U19")
      (value "IC_BITFURY16")
      (footprint "SMD_QFN50P600X600X175-36AN")
      (description "BitFury 2016 16 nm")
      (libsource (lib "BitCoin") (part "IC_BITFURY16"))
    )
    (comp (ref "U20")
      (value "IC_BITFURY16")
      (footprint "SMD_QFN50P600X600X175-36AN")
      (description "BitFury 2016 16 nm")
      (libsource (lib "BitCoin") (part "IC_BITFURY16"))
    )
    (comp (ref "U21")
      (value "IC_BTC250")
      (footprint "SMD_QFN40P500X500X80-41N")
      (fields (field (name "DB_MANUFACTURER_PART") "BTC250 QFN40 EP"))
      (libsource (lib "BitCoin") (part "IC_BTC250"))
    )
    (comp (ref "U22")
      (value "IC_BITFURY16")
      (footprint "SMD_QFN50P600X600X175-36AN")
      (description "BitFury 2016 16 nm")
      (libsource (lib "BitCoin") (part "IC_BITFURY16"))
    )
    (comp (ref "U23")
      (value "IC_BITFURY16")
      (footprint "SMD_QFN50P600X600X175-36AN")
      (description "BitFury 2016 16 nm")
      (libsource (lib "BitCoin") (part "IC_BITFURY16"))
    )
    (comp (ref "U24")
      (value "IC_BITFURY16")
      (footprint "SMD_QFN50P600X600X175-36AN")
      (description "BitFury 2016 16 nm")
      (libsource (lib "BitCoin") (part "IC_BITFURY16"))
    )
  )
  (nets
    (net (code "1") (name "/BF_CLK0") (class "Default")
      (node (ref "U13") (pin "22") (pinfunction "SCK_22") (pintype "passive"))
      (node (ref "U21") (pin "10") (pinfunction "C_0_10") (pintype "passive"))
    )
    (net (code "2") (name "/BF_CLK1") (class "Default")
      (node (ref "U14") (pin "22") (pinfunction "SCK_22") (pintype "passive"))
      (node (ref "U21") (pin "7") (pinfunction "C_1_7") (pintype "passive"))
    )
    (net (code "3") (name "/BF_CLK2") (class "Default")
      (node (ref "U15") (pin "22") (pinfunction "SCK_22") (pintype "passive"))
      (node (ref "U21") (pin "4") (pinfunction "C_2_4") (pintype "passive"))
    )
    (net (code "4") (name "/BF_CLK3") (class "Default")
      (node (ref "U16") (pin "22") (pinfunction "SCK_22") (pintype "passive"))
      (node (ref "U21") (pin "1") (pinfunction "C_3_1") (pintype "passive"))
    )
    (net (code "5") (name "/BF_CLK4") (class "Default")
      (node (ref "U17") (pin "22") (pinfunction "SCK_22") (pintype "passive"))
      (node (ref "U21") (pin "38") (pinfunction "C_4_38") (pintype "passive"))
    )
    (net (code "6") (name "/BF_CLK5") (class "Default")
      (node (ref "U18") (pin "22") (pinfunction "SCK_22") (pintype "passive"))
      (node (ref "U21") (pin "35") (pinfunction "C_5_35") (pintype "passive"))
    )
    (net (code "7") (name "/BF_CLK6") (class "Default")
      (node (ref "U19") (pin "22") (pinfunction "SCK_22") (pintype "passive"))
      (node (ref "U21") (pin "32") (pinfunction "C_6_32") (pintype "passive"))
    )
    (net (code "8") (name "/BF_CLK7") (class "Default")
      (node (ref "U20") (pin "22") (pinfunction "SCK_22") (pintype "passive"))
      (node (ref "U21") (pin "29") (pinfunction "C_7_29") (pintype "passive"))
    )
    (net (code "9") (name "/BF_CLK8") (class "Default")
      (node (ref "U21") (pin "26") (pinfunction "C_8_26") (pintype "passive"))
      (node (ref "U22") (pin "22") (pinfunction "SCK_22") (pintype "passive"))
    )
    (net (code "10") (name "/BF_CLK9") (class "Default")
      (node (ref "U21") (pin "23") (pinfunction "C_9_23") (pintype "passive"))
      (node (ref "U23") (pin "22") (pinfunction "SCK_22") (pintype "passive"))
    )
    (net (code "11") (name "/BF_CLK10") (class "Default")
      (node (ref "U21") (pin "20") (pinfunction "C_10_20") (pintype "passive"))
      (node (ref "U24") (pin "22") (pinfunction "SCK_22") (pintype "passive"))
    )
    (net (code "12") (name "/BF_DAT0") (class "Default")
      (node (ref "U13") (pin "23") (pinfunction "SDATA_23") (pintype "passive"))
      (node (ref "U21") (pin "9") (pinfunction "D_0_9") (pintype "passive"))
    )
    (net (code "13") (name "/BF_DAT1") (class "Default")
      (node (ref "U14") (pin "23") (pinfunction "SDATA_23") (pintype "passive"))
      (node (ref "U21") (pin "6") (pinfunction "D_1_6") (pintype "passive"))
    )
    (net (code "14") (name "/BF_DAT2") (class "Default")
      (node (ref "U15") (pin "23") (pinfunction "SDATA_23") (pintype "passive"))
      (node (ref "U21") (pin "3") (pinfunction "D_2_3") (pintype "passive"))
    )
    (net (code "15") (name "/BF_DAT3") (class "Default")
      (node (ref "U16") (pin "23") (pinfunction "SDATA_23") (pintype "passive"))
      (node (ref "U21") (pin "40") (pinfunction "D_3_40") (pintype "passive"))
    )
    (net (code "16") (name "/BF_DAT4") (class "Default")
      (node (ref "U17") (pin "23") (pinfunction "SDATA_23") (pintype "passive"))
      (node (ref "U21") (pin "37") (pinfunction "D_4_37") (pintype "passive"))
    )
    (net (code "17") (name "/BF_DAT5") (class "Default")
      (node (ref "U18") (pin "23") (pinfunction "SDATA_23") (pintype "passive"))
      (node (ref "U21") (pin "34") (pinfunction "D_5_34") (pintype "passive"))
    )
    (net (code "18") (name "/BF_DAT6") (class "Default")
      (node (ref "U19") (pin "23") (pinfunction "SDATA_23") (pintype "passive"))
      (node (ref "U21") (pin "31") (pinfunction "D_6_31") (pintype "passive"))
    )
    (net (code "19") (name "/BF_DAT7") (class "Default")
      (node (ref "U20") (pin "23") (pinfunction "SDATA_23") (pintype "passive"))
      (node (ref "U21") (pin "28") (pinfunction "D_7_28") (pintype "passive"))
    )
    (net (code "20") (name "/BF_DAT8") (class "Default")
      (node (ref "U21") (pin "25") (pinfunction "D_8_25") (pintype "passive"))
      (node (ref "U22") (pin "23") (pinfunction "SDATA_23") (pintype "passive"))
    )
    (net (code "21") (name "/BF_DAT9") (class "Default")
      (node (ref "U21") (pin "22") (pinfunction "D_9_22") (pintype "passive"))
      (node (ref "U23") (pin "23") (pinfunction "SDATA_23") (pintype "passive"))
    )
    (net (code "22") (name "/BF_DAT10") (class "Default")
      (node (ref "U21") (pin "19") (pinfunction "D_10_19") (pintype "passive"))
      (node (ref "U24") (pin "23") (pinfunction "SDATA_23") (pintype "passive"))
    )
    (net (code "23") (name "/PAR_1") (class "Default")
      (node (ref "U21") (pin "18") (pinfunction "PARITY_18") (pintype "passive"))
    )
    (net (code "24") (name "/PWR0") (class "Default")
      (node (ref "C120") (pin "2") (pinfunction "2_2") (pintype "passive"))
      (node (ref "C72") (pin "2") (pinfunction "2_2") (pintype "passive"))
      (node (ref "C73") (pin "2") (pinfunction "2_2") (pintype "passive"))
      (node (ref "C74") (pin "2") (pinfunction "2_2") (pintype "passive"))
      (node (ref "C84") (pin "2") (pinfunction "2_2") (pintype "passive"))
      (node (ref "C85") (pin "2") (pinfunction "2_2") (pintype "passive"))
      (node (ref "C86") (pin "2") (pinfunction "2_2") (pintype "passive"))
      (node (ref "U13") (pin "36") (pinfunction "EP_36") (pintype "passive"))
      (node (ref "U21") (pin "41") (pinfunction "VSS_41") (pintype "passive"))
    )
    (net (code "25") (name "/PWR1") (class "Default")
      (node (ref "C72") (pin "1") (pinfunction "1_1") (pintype "passive"))
      (node (ref "C73") (pin "1") (pinfunction "1_1") (pintype "passive"))
      (node (ref "C74") (pin "1") (pinfunction "1_1") (pintype "passive"))
      (node (ref "C75") (pin "2") (pinfunction "2_2") (pintype "passive"))
      (node (ref "C76") (pin "2") (pinfunction "2_2") (pintype "passive"))
      (node (ref "C77") (pin "2") (pinfunction "2_2") (pintype "passive"))
      (node (ref "C84") (pin "1") (pinfunction "1_1") (pintype "passive"))
      (node (ref "C85") (pin "1") (pinfunction "1_1") (pintype "passive"))
      (node (ref "C86") (pin "1") (pinfunction "1_1") (pintype "passive"))
      (node (ref "C87") (pin "2") (pinfunction "2_2") (pintype "passive"))
      (node (ref "C88") (pin "2") (pinfunction "2_2") (pintype "passive"))
      (node (ref "C89") (pin "2") (pinfunction "2_2") (pintype "passive"))
      (node (ref "U13") (pin "1") (pinfunction "VDD_1") (pintype "passive"))
      (node (ref "U13") (pin "10") (pinfunction "VDD_10") (pintype "passive"))
      (node (ref "U13") (pin "11") (pinfunction "VDD_11") (pintype "passive"))
      (node (ref "U13") (pin "12") (pinfunction "VDD_12") (pintype "passive"))
      (node (ref "U13") (pin "13") (pinfunction "VDD_13") (pintype "passive"))
      (node (ref "U13") (pin "14") (pinfunction "VDD_14") (pintype "passive"))
      (node (ref "U13") (pin "15") (pinfunction "VDD_15") (pintype "passive"))
      (node (ref "U13") (pin "16") (pinfunction "VDD_16") (pintype "passive"))
      (node (ref "U13") (pin "17") (pinfunction "VDD_17") (pintype "passive"))
      (node (ref "U13") (pin "18") (pinfunction "VDD_18") (pintype "passive"))
      (node (ref "U13") (pin "19") (pinfunction "VDD_19") (pintype "passive"))
      (node (ref "U13") (pin "2") (pinfunction "VDD_2") (pintype "passive"))
      (node (ref "U13") (pin "20") (pinfunction "VDD_20") (pintype "passive"))
      (node (ref "U13") (pin "21") (pinfunction "VDD_21") (pintype "passive"))
      (node (ref "U13") (pin "24") (pinfunction "VDD_24") (pintype "passive"))
      (node (ref "U13") (pin "25") (pinfunction "VDD_25") (pintype "passive"))
      (node (ref "U13") (pin "26") (pinfunction "VDD_26") (pintype "passive"))
      (node (ref "U13") (pin "27") (pinfunction "VDD_27") (pintype "passive"))
      (node (ref "U13") (pin "28") (pinfunction "VDD_28") (pintype "passive"))
      (node (ref "U13") (pin "29") (pinfunction "VDD_29") (pintype "passive"))
      (node (ref "U13") (pin "3") (pinfunction "VDD_3") (pintype "passive"))
      (node (ref "U13") (pin "30") (pinfunction "VDD_30") (pintype "passive"))
      (node (ref "U13") (pin "31") (pinfunction "VDD_31") (pintype "passive"))
      (node (ref "U13") (pin "32") (pinfunction "VDD_32") (pintype "passive"))
      (node (ref "U13") (pin "33") (pinfunction "VDD_33") (pintype "passive"))
      (node (ref "U13") (pin "34") (pinfunction "VDD_34") (pintype "passive"))
      (node (ref "U13") (pin "35") (pinfunction "VDD_35") (pintype "passive"))
      (node (ref "U13") (pin "4") (pinfunction "VDD_4") (pintype "passive"))
      (node (ref "U13") (pin "5") (pinfunction "VDD_5") (pintype "passive"))
      (node (ref "U13") (pin "6") (pinfunction "VDD_6") (pintype "passive"))
      (node (ref "U13") (pin "7") (pinfunction "VDD_7") (pintype "passive"))
      (node (ref "U13") (pin "8") (pinfunction "VDD_8") (pintype "passive"))
      (node (ref "U13") (pin "9") (pinfunction "VDD_9") (pintype "passive"))
      (node (ref "U14") (pin "36") (pinfunction "EP_36") (pintype "passive"))
      (node (ref "U21") (pin "8") (pinfunction "V_0_8") (pintype "passive"))
    )
    (net (code "26") (name "/PWR2") (class "Default")
      (node (ref "C75") (pin "1") (pinfunction "1_1") (pintype "passive"))
      (node (ref "C76") (pin "1") (pinfunction "1_1") (pintype "passive"))
      (node (ref "C77") (pin "1") (pinfunction "1_1") (pintype "passive"))
      (node (ref "C78") (pin "2") (pinfunction "2_2") (pintype "passive"))
      (node (ref "C79") (pin "2") (pinfunction "2_2") (pintype "passive"))
      (node (ref "C80") (pin "2") (pinfunction "2_2") (pintype "passive"))
      (node (ref "C87") (pin "1") (pinfunction "1_1") (pintype "passive"))
      (node (ref "C88") (pin "1") (pinfunction "1_1") (pintype "passive"))
      (node (ref "C89") (pin "1") (pinfunction "1_1") (pintype "passive"))
      (node (ref "C90") (pin "2") (pinfunction "2_2") (pintype "passive"))
      (node (ref "C91") (pin "2") (pinfunction "2_2") (pintype "passive"))
      (node (ref "C92") (pin "2") (pinfunction "2_2") (pintype "passive"))
      (node (ref "U14") (pin "1") (pinfunction "VDD_1") (pintype "passive"))
      (node (ref "U14") (pin "10") (pinfunction "VDD_10") (pintype "passive"))
      (node (ref "U14") (pin "11") (pinfunction "VDD_11") (pintype "passive"))
      (node (ref "U14") (pin "12") (pinfunction "VDD_12") (pintype "passive"))
      (node (ref "U14") (pin "13") (pinfunction "VDD_13") (pintype "passive"))
      (node (ref "U14") (pin "14") (pinfunction "VDD_14") (pintype "passive"))
      (node (ref "U14") (pin "15") (pinfunction "VDD_15") (pintype "passive"))
      (node (ref "U14") (pin "16") (pinfunction "VDD_16") (pintype "passive"))
      (node (ref "U14") (pin "17") (pinfunction "VDD_17") (pintype "passive"))
      (node (ref "U14") (pin "18") (pinfunction "VDD_18") (pintype "passive"))
      (node (ref "U14") (pin "19") (pinfunction "VDD_19") (pintype "passive"))
      (node (ref "U14") (pin "2") (pinfunction "VDD_2") (pintype "passive"))
      (node (ref "U14") (pin "20") (pinfunction "VDD_20") (pintype "passive"))
      (node (ref "U14") (pin "21") (pinfunction "VDD_21") (pintype "passive"))
      (node (ref "U14") (pin "24") (pinfunction "VDD_24") (pintype "passive"))
      (node (ref "U14") (pin "25") (pinfunction "VDD_25") (pintype "passive"))
      (node (ref "U14") (pin "26") (pinfunction "VDD_26") (pintype "passive"))
      (node (ref "U14") (pin "27") (pinfunction "VDD_27") (pintype "passive"))
      (node (ref "U14") (pin "28") (pinfunction "VDD_28") (pintype "passive"))
      (node (ref "U14") (pin "29") (pinfunction "VDD_29") (pintype "passive"))
      (node (ref "U14") (pin "3") (pinfunction "VDD_3") (pintype "passive"))
      (node (ref "U14") (pin "30") (pinfunction "VDD_30") (pintype "passive"))
      (node (ref "U14") (pin "31") (pinfunction "VDD_31") (pintype "passive"))
      (node (ref "U14") (pin "32") (pinfunction "VDD_32") (pintype "passive"))
      (node (ref "U14") (pin "33") (pinfunction "VDD_33") (pintype "passive"))
      (node (ref "U14") (pin "34") (pinfunction "VDD_34") (pintype "passive"))
      (node (ref "U14") (pin "35") (pinfunction "VDD_35") (pintype "passive"))
      (node (ref "U14") (pin "4") (pinfunction "VDD_4") (pintype "passive"))
      (node (ref "U14") (pin "5") (pinfunction "VDD_5") (pintype "passive"))
      (node (ref "U14") (pin "6") (pinfunction "VDD_6") (pintype "passive"))
      (node (ref "U14") (pin "7") (pinfunction "VDD_7") (pintype "passive"))
      (node (ref "U14") (pin "8") (pinfunction "VDD_8") (pintype "passive"))
      (node (ref "U14") (pin "9") (pinfunction "VDD_9") (pintype "passive"))
      (node (ref "U15") (pin "36") (pinfunction "EP_36") (pintype "passive"))
      (node (ref "U21") (pin "5") (pinfunction "V_1_5") (pintype "passive"))
    )
    (net (code "27") (name "/PWR3") (class "Default")
      (node (ref "C78") (pin "1") (pinfunction "1_1") (pintype "passive"))
      (node (ref "C79") (pin "1") (pinfunction "1_1") (pintype "passive"))
      (node (ref "C80") (pin "1") (pinfunction "1_1") (pintype "passive"))
      (node (ref "C81") (pin "2") (pinfunction "2_2") (pintype "passive"))
      (node (ref "C82") (pin "2") (pinfunction "2_2") (pintype "passive"))
      (node (ref "C83") (pin "2") (pinfunction "2_2") (pintype "passive"))
      (node (ref "C90") (pin "1") (pinfunction "1_1") (pintype "passive"))
      (node (ref "C91") (pin "1") (pinfunction "1_1") (pintype "passive"))
      (node (ref "C92") (pin "1") (pinfunction "1_1") (pintype "passive"))
      (node (ref "C93") (pin "2") (pinfunction "2_2") (pintype "passive"))
      (node (ref "C94") (pin "2") (pinfunction "2_2") (pintype "passive"))
      (node (ref "C95") (pin "2") (pinfunction "2_2") (pintype "passive"))
      (node (ref "U15") (pin "1") (pinfunction "VDD_1") (pintype "passive"))
      (node (ref "U15") (pin "10") (pinfunction "VDD_10") (pintype "passive"))
      (node (ref "U15") (pin "11") (pinfunction "VDD_11") (pintype "passive"))
      (node (ref "U15") (pin "12") (pinfunction "VDD_12") (pintype "passive"))
      (node (ref "U15") (pin "13") (pinfunction "VDD_13") (pintype "passive"))
      (node (ref "U15") (pin "14") (pinfunction "VDD_14") (pintype "passive"))
      (node (ref "U15") (pin "15") (pinfunction "VDD_15") (pintype "passive"))
      (node (ref "U15") (pin "16") (pinfunction "VDD_16") (pintype "passive"))
      (node (ref "U15") (pin "17") (pinfunction "VDD_17") (pintype "passive"))
      (node (ref "U15") (pin "18") (pinfunction "VDD_18") (pintype "passive"))
      (node (ref "U15") (pin "19") (pinfunction "VDD_19") (pintype "passive"))
      (node (ref "U15") (pin "2") (pinfunction "VDD_2") (pintype "passive"))
      (node (ref "U15") (pin "20") (pinfunction "VDD_20") (pintype "passive"))
      (node (ref "U15") (pin "21") (pinfunction "VDD_21") (pintype "passive"))
      (node (ref "U15") (pin "24") (pinfunction "VDD_24") (pintype "passive"))
      (node (ref "U15") (pin "25") (pinfunction "VDD_25") (pintype "passive"))
      (node (ref "U15") (pin "26") (pinfunction "VDD_26") (pintype "passive"))
      (node (ref "U15") (pin "27") (pinfunction "VDD_27") (pintype "passive"))
      (node (ref "U15") (pin "28") (pinfunction "VDD_28") (pintype "passive"))
      (node (ref "U15") (pin "29") (pinfunction "VDD_29") (pintype "passive"))
      (node (ref "U15") (pin "3") (pinfunction "VDD_3") (pintype "passive"))
      (node (ref "U15") (pin "30") (pinfunction "VDD_30") (pintype "passive"))
      (node (ref "U15") (pin "31") (pinfunction "VDD_31") (pintype "passive"))
      (node (ref "U15") (pin "32") (pinfunction "VDD_32") (pintype "passive"))
      (node (ref "U15") (pin "33") (pinfunction "VDD_33") (pintype "passive"))
      (node (ref "U15") (pin "34") (pinfunction "VDD_34") (pintype "passive"))
      (node (ref "U15") (pin "35") (pinfunction "VDD_35") (pintype "passive"))
      (node (ref "U15") (pin "4") (pinfunction "VDD_4") (pintype "passive"))
      (node (ref "U15") (pin "5") (pinfunction "VDD_5") (pintype "passive"))
      (node (ref "U15") (pin "6") (pinfunction "VDD_6") (pintype "passive"))
      (node (ref "U15") (pin "7") (pinfunction "VDD_7") (pintype "passive"))
      (node (ref "U15") (pin "8") (pinfunction "VDD_8") (pintype "passive"))
      (node (ref "U15") (pin "9") (pinfunction "VDD_9") (pintype "passive"))
      (node (ref "U16") (pin "36") (pinfunction "EP_36") (pintype "passive"))
      (node (ref "U21") (pin "2") (pinfunction "V_2_2") (pintype "passive"))
    )
    (net (code "28") (name "/PWR4") (class "Default")
      (node (ref "C108") (pin "2") (pinfunction "2_2") (pintype "passive"))
      (node (ref "C109") (pin "2") (pinfunction "2_2") (pintype "passive"))
      (node (ref "C110") (pin "2") (pinfunction "2_2") (pintype "passive"))
      (node (ref "C81") (pin "1") (pinfunction "1_1") (pintype "passive"))
      (node (ref "C82") (pin "1") (pinfunction "1_1") (pintype "passive"))
      (node (ref "C83") (pin "1") (pinfunction "1_1") (pintype "passive"))
      (node (ref "C93") (pin "1") (pinfunction "1_1") (pintype "passive"))
      (node (ref "C94") (pin "1") (pinfunction "1_1") (pintype "passive"))
      (node (ref "C95") (pin "1") (pinfunction "1_1") (pintype "passive"))
      (node (ref "C96") (pin "2") (pinfunction "2_2") (pintype "passive"))
      (node (ref "C97") (pin "2") (pinfunction "2_2") (pintype "passive"))
      (node (ref "C98") (pin "2") (pinfunction "2_2") (pintype "passive"))
      (node (ref "U16") (pin "1") (pinfunction "VDD_1") (pintype "passive"))
      (node (ref "U16") (pin "10") (pinfunction "VDD_10") (pintype "passive"))
      (node (ref "U16") (pin "11") (pinfunction "VDD_11") (pintype "passive"))
      (node (ref "U16") (pin "12") (pinfunction "VDD_12") (pintype "passive"))
      (node (ref "U16") (pin "13") (pinfunction "VDD_13") (pintype "passive"))
      (node (ref "U16") (pin "14") (pinfunction "VDD_14") (pintype "passive"))
      (node (ref "U16") (pin "15") (pinfunction "VDD_15") (pintype "passive"))
      (node (ref "U16") (pin "16") (pinfunction "VDD_16") (pintype "passive"))
      (node (ref "U16") (pin "17") (pinfunction "VDD_17") (pintype "passive"))
      (node (ref "U16") (pin "18") (pinfunction "VDD_18") (pintype "passive"))
      (node (ref "U16") (pin "19") (pinfunction "VDD_19") (pintype "passive"))
      (node (ref "U16") (pin "2") (pinfunction "VDD_2") (pintype "passive"))
      (node (ref "U16") (pin "20") (pinfunction "VDD_20") (pintype "passive"))
      (node (ref "U16") (pin "21") (pinfunction "VDD_21") (pintype "passive"))
      (node (ref "U16") (pin "24") (pinfunction "VDD_24") (pintype "passive"))
      (node (ref "U16") (pin "25") (pinfunction "VDD_25") (pintype "passive"))
      (node (ref "U16") (pin "26") (pinfunction "VDD_26") (pintype "passive"))
      (node (ref "U16") (pin "27") (pinfunction "VDD_27") (pintype "passive"))
      (node (ref "U16") (pin "28") (pinfunction "VDD_28") (pintype "passive"))
      (node (ref "U16") (pin "29") (pinfunction "VDD_29") (pintype "passive"))
      (node (ref "U16") (pin "3") (pinfunction "VDD_3") (pintype "passive"))
      (node (ref "U16") (pin "30") (pinfunction "VDD_30") (pintype "passive"))
      (node (ref "U16") (pin "31") (pinfunction "VDD_31") (pintype "passive"))
      (node (ref "U16") (pin "32") (pinfunction "VDD_32") (pintype "passive"))
      (node (ref "U16") (pin "33") (pinfunction "VDD_33") (pintype "passive"))
      (node (ref "U16") (pin "34") (pinfunction "VDD_34") (pintype "passive"))
      (node (ref "U16") (pin "35") (pinfunction "VDD_35") (pintype "passive"))
      (node (ref "U16") (pin "4") (pinfunction "VDD_4") (pintype "passive"))
      (node (ref "U16") (pin "5") (pinfunction "VDD_5") (pintype "passive"))
      (node (ref "U16") (pin "6") (pinfunction "VDD_6") (pintype "passive"))
      (node (ref "U16") (pin "7") (pinfunction "VDD_7") (pintype "passive"))
      (node (ref "U16") (pin "8") (pinfunction "VDD_8") (pintype "passive"))
      (node (ref "U16") (pin "9") (pinfunction "VDD_9") (pintype "passive"))
      (node (ref "U17") (pin "36") (pinfunction "EP_36") (pintype "passive"))
      (node (ref "U21") (pin "39") (pinfunction "V_3_39") (pintype "passive"))
    )
    (net (code "29") (name "/PWR5") (class "Default")
      (node (ref "C100") (pin "2") (pinfunction "2_2") (pintype "passive"))
      (node (ref "C101") (pin "2") (pinfunction "2_2") (pintype "passive"))
      (node (ref "C108") (pin "1") (pinfunction "1_1") (pintype "passive"))
      (node (ref "C109") (pin "1") (pinfunction "1_1") (pintype "passive"))
      (node (ref "C110") (pin "1") (pinfunction "1_1") (pintype "passive"))
      (node (ref "C111") (pin "2") (pinfunction "2_2") (pintype "passive"))
      (node (ref "C112") (pin "2") (pinfunction "2_2") (pintype "passive"))
      (node (ref "C113") (pin "2") (pinfunction "2_2") (pintype "passive"))
      (node (ref "C96") (pin "1") (pinfunction "1_1") (pintype "passive"))
      (node (ref "C97") (pin "1") (pinfunction "1_1") (pintype "passive"))
      (node (ref "C98") (pin "1") (pinfunction "1_1") (pintype "passive"))
      (node (ref "C99") (pin "2") (pinfunction "2_2") (pintype "passive"))
      (node (ref "U17") (pin "1") (pinfunction "VDD_1") (pintype "passive"))
      (node (ref "U17") (pin "10") (pinfunction "VDD_10") (pintype "passive"))
      (node (ref "U17") (pin "11") (pinfunction "VDD_11") (pintype "passive"))
      (node (ref "U17") (pin "12") (pinfunction "VDD_12") (pintype "passive"))
      (node (ref "U17") (pin "13") (pinfunction "VDD_13") (pintype "passive"))
      (node (ref "U17") (pin "14") (pinfunction "VDD_14") (pintype "passive"))
      (node (ref "U17") (pin "15") (pinfunction "VDD_15") (pintype "passive"))
      (node (ref "U17") (pin "16") (pinfunction "VDD_16") (pintype "passive"))
      (node (ref "U17") (pin "17") (pinfunction "VDD_17") (pintype "passive"))
      (node (ref "U17") (pin "18") (pinfunction "VDD_18") (pintype "passive"))
      (node (ref "U17") (pin "19") (pinfunction "VDD_19") (pintype "passive"))
      (node (ref "U17") (pin "2") (pinfunction "VDD_2") (pintype "passive"))
      (node (ref "U17") (pin "20") (pinfunction "VDD_20") (pintype "passive"))
      (node (ref "U17") (pin "21") (pinfunction "VDD_21") (pintype "passive"))
      (node (ref "U17") (pin "24") (pinfunction "VDD_24") (pintype "passive"))
      (node (ref "U17") (pin "25") (pinfunction "VDD_25") (pintype "passive"))
      (node (ref "U17") (pin "26") (pinfunction "VDD_26") (pintype "passive"))
      (node (ref "U17") (pin "27") (pinfunction "VDD_27") (pintype "passive"))
      (node (ref "U17") (pin "28") (pinfunction "VDD_28") (pintype "passive"))
      (node (ref "U17") (pin "29") (pinfunction "VDD_29") (pintype "passive"))
      (node (ref "U17") (pin "3") (pinfunction "VDD_3") (pintype "passive"))
      (node (ref "U17") (pin "30") (pinfunction "VDD_30") (pintype "passive"))
      (node (ref "U17") (pin "31") (pinfunction "VDD_31") (pintype "passive"))
      (node (ref "U17") (pin "32") (pinfunction "VDD_32") (pintype "passive"))
      (node (ref "U17") (pin "33") (pinfunction "VDD_33") (pintype "passive"))
      (node (ref "U17") (pin "34") (pinfunction "VDD_34") (pintype "passive"))
      (node (ref "U17") (pin "35") (pinfunction "VDD_35") (pintype "passive"))
      (node (ref "U17") (pin "4") (pinfunction "VDD_4") (pintype "passive"))
      (node (ref "U17") (pin "5") (pinfunction "VDD_5") (pintype "passive"))
      (node (ref "U17") (pin "6") (pinfunction "VDD_6") (pintype "passive"))
      (node (ref "U17") (pin "7") (pinfunction "VDD_7") (pintype "passive"))
      (node (ref "U17") (pin "8") (pinfunction "VDD_8") (pintype "passive"))
      (node (ref "U17") (pin "9") (pinfunction "VDD_9") (pintype "passive"))
      (node (ref "U18") (pin "36") (pinfunction "EP_36") (pintype "passive"))
      (node (ref "U21") (pin "36") (pinfunction "V_4_36") (pintype "passive"))
    )
    (net (code "30") (name "/PWR6") (class "Default")
      (node (ref "C100") (pin "1") (pinfunction "1_1") (pintype "passive"))
      (node (ref "C101") (pin "1") (pinfunction "1_1") (pintype "passive"))
      (node (ref "C102") (pin "2") (pinfunction "2_2") (pintype "passive"))
      (node (ref "C103") (pin "2") (pinfunction "2_2") (pintype "passive"))
      (node (ref "C104") (pin "2") (pinfunction "2_2") (pintype "passive"))
      (node (ref "C111") (pin "1") (pinfunction "1_1") (pintype "passive"))
      (node (ref "C112") (pin "1") (pinfunction "1_1") (pintype "passive"))
      (node (ref "C113") (pin "1") (pinfunction "1_1") (pintype "passive"))
      (node (ref "C114") (pin "2") (pinfunction "2_2") (pintype "passive"))
      (node (ref "C115") (pin "2") (pinfunction "2_2") (pintype "passive"))
      (node (ref "C116") (pin "2") (pinfunction "2_2") (pintype "passive"))
      (node (ref "C99") (pin "1") (pinfunction "1_1") (pintype "passive"))
      (node (ref "U18") (pin "1") (pinfunction "VDD_1") (pintype "passive"))
      (node (ref "U18") (pin "10") (pinfunction "VDD_10") (pintype "passive"))
      (node (ref "U18") (pin "11") (pinfunction "VDD_11") (pintype "passive"))
      (node (ref "U18") (pin "12") (pinfunction "VDD_12") (pintype "passive"))
      (node (ref "U18") (pin "13") (pinfunction "VDD_13") (pintype "passive"))
      (node (ref "U18") (pin "14") (pinfunction "VDD_14") (pintype "passive"))
      (node (ref "U18") (pin "15") (pinfunction "VDD_15") (pintype "passive"))
      (node (ref "U18") (pin "16") (pinfunction "VDD_16") (pintype "passive"))
      (node (ref "U18") (pin "17") (pinfunction "VDD_17") (pintype "passive"))
      (node (ref "U18") (pin "18") (pinfunction "VDD_18") (pintype "passive"))
      (node (ref "U18") (pin "19") (pinfunction "VDD_19") (pintype "passive"))
      (node (ref "U18") (pin "2") (pinfunction "VDD_2") (pintype "passive"))
      (node (ref "U18") (pin "20") (pinfunction "VDD_20") (pintype "passive"))
      (node (ref "U18") (pin "21") (pinfunction "VDD_21") (pintype "passive"))
      (node (ref "U18") (pin "24") (pinfunction "VDD_24") (pintype "passive"))
      (node (ref "U18") (pin "25") (pinfunction "VDD_25") (pintype "passive"))
      (node (ref "U18") (pin "26") (pinfunction "VDD_26") (pintype "passive"))
      (node (ref "U18") (pin "27") (pinfunction "VDD_27") (pintype "passive"))
      (node (ref "U18") (pin "28") (pinfunction "VDD_28") (pintype "passive"))
      (node (ref "U18") (pin "29") (pinfunction "VDD_29") (pintype "passive"))
      (node (ref "U18") (pin "3") (pinfunction "VDD_3") (pintype "passive"))
      (node (ref "U18") (pin "30") (pinfunction "VDD_30") (pintype "passive"))
      (node (ref "U18") (pin "31") (pinfunction "VDD_31") (pintype "passive"))
      (node (ref "U18") (pin "32") (pinfunction "VDD_32") (pintype "passive"))
      (node (ref "U18") (pin "33") (pinfunction "VDD_33") (pintype "passive"))
      (node (ref "U18") (pin "34") (pinfunction "VDD_34") (pintype "passive"))
      (node (ref "U18") (pin "35") (pinfunction "VDD_35") (pintype "passive"))
      (node (ref "U18") (pin "4") (pinfunction "VDD_4") (pintype "passive"))
      (node (ref "U18") (pin "5") (pinfunction "VDD_5") (pintype "passive"))
      (node (ref "U18") (pin "6") (pinfunction "VDD_6") (pintype "passive"))
      (node (ref "U18") (pin "7") (pinfunction "VDD_7") (pintype "passive"))
      (node (ref "U18") (pin "8") (pinfunction "VDD_8") (pintype "passive"))
      (node (ref "U18") (pin "9") (pinfunction "VDD_9") (pintype "passive"))
      (node (ref "U19") (pin "36") (pinfunction "EP_36") (pintype "passive"))
      (node (ref "U21") (pin "33") (pinfunction "V_5_33") (pintype "passive"))
    )
    (net (code "31") (name "/PWR7") (class "Default")
      (node (ref "C102") (pin "1") (pinfunction "1_1") (pintype "passive"))
      (node (ref "C103") (pin "1") (pinfunction "1_1") (pintype "passive"))
      (node (ref "C104") (pin "1") (pinfunction "1_1") (pintype "passive"))
      (node (ref "C105") (pin "2") (pinfunction "2_2") (pintype "passive"))
      (node (ref "C106") (pin "2") (pinfunction "2_2") (pintype "passive"))
      (node (ref "C107") (pin "2") (pinfunction "2_2") (pintype "passive"))
      (node (ref "C114") (pin "1") (pinfunction "1_1") (pintype "passive"))
      (node (ref "C115") (pin "1") (pinfunction "1_1") (pintype "passive"))
      (node (ref "C116") (pin "1") (pinfunction "1_1") (pintype "passive"))
      (node (ref "C117") (pin "2") (pinfunction "2_2") (pintype "passive"))
      (node (ref "C118") (pin "2") (pinfunction "2_2") (pintype "passive"))
      (node (ref "C119") (pin "2") (pinfunction "2_2") (pintype "passive"))
      (node (ref "U19") (pin "1") (pinfunction "VDD_1") (pintype "passive"))
      (node (ref "U19") (pin "10") (pinfunction "VDD_10") (pintype "passive"))
      (node (ref "U19") (pin "11") (pinfunction "VDD_11") (pintype "passive"))
      (node (ref "U19") (pin "12") (pinfunction "VDD_12") (pintype "passive"))
      (node (ref "U19") (pin "13") (pinfunction "VDD_13") (pintype "passive"))
      (node (ref "U19") (pin "14") (pinfunction "VDD_14") (pintype "passive"))
      (node (ref "U19") (pin "15") (pinfunction "VDD_15") (pintype "passive"))
      (node (ref "U19") (pin "16") (pinfunction "VDD_16") (pintype "passive"))
      (node (ref "U19") (pin "17") (pinfunction "VDD_17") (pintype "passive"))
      (node (ref "U19") (pin "18") (pinfunction "VDD_18") (pintype "passive"))
      (node (ref "U19") (pin "19") (pinfunction "VDD_19") (pintype "passive"))
      (node (ref "U19") (pin "2") (pinfunction "VDD_2") (pintype "passive"))
      (node (ref "U19") (pin "20") (pinfunction "VDD_20") (pintype "passive"))
      (node (ref "U19") (pin "21") (pinfunction "VDD_21") (pintype "passive"))
      (node (ref "U19") (pin "24") (pinfunction "VDD_24") (pintype "passive"))
      (node (ref "U19") (pin "25") (pinfunction "VDD_25") (pintype "passive"))
      (node (ref "U19") (pin "26") (pinfunction "VDD_26") (pintype "passive"))
      (node (ref "U19") (pin "27") (pinfunction "VDD_27") (pintype "passive"))
      (node (ref "U19") (pin "28") (pinfunction "VDD_28") (pintype "passive"))
      (node (ref "U19") (pin "29") (pinfunction "VDD_29") (pintype "passive"))
      (node (ref "U19") (pin "3") (pinfunction "VDD_3") (pintype "passive"))
      (node (ref "U19") (pin "30") (pinfunction "VDD_30") (pintype "passive"))
      (node (ref "U19") (pin "31") (pinfunction "VDD_31") (pintype "passive"))
      (node (ref "U19") (pin "32") (pinfunction "VDD_32") (pintype "passive"))
      (node (ref "U19") (pin "33") (pinfunction "VDD_33") (pintype "passive"))
      (node (ref "U19") (pin "34") (pinfunction "VDD_34") (pintype "passive"))
      (node (ref "U19") (pin "35") (pinfunction "VDD_35") (pintype "passive"))
      (node (ref "U19") (pin "4") (pinfunction "VDD_4") (pintype "passive"))
      (node (ref "U19") (pin "5") (pinfunction "VDD_5") (pintype "passive"))
      (node (ref "U19") (pin "6") (pinfunction "VDD_6") (pintype "passive"))
      (node (ref "U19") (pin "7") (pinfunction "VDD_7") (pintype "passive"))
      (node (ref "U19") (pin "8") (pinfunction "VDD_8") (pintype "passive"))
      (node (ref "U19") (pin "9") (pinfunction "VDD_9") (pintype "passive"))
      (node (ref "U20") (pin "36") (pinfunction "EP_36") (pintype "passive"))
      (node (ref "U21") (pin "30") (pinfunction "V_6_30") (pintype "passive"))
    )
    (net (code "32") (name "/PWR8") (class "Default")
      (node (ref "C105") (pin "1") (pinfunction "1_1") (pintype "passive"))
      (node (ref "C106") (pin "1") (pinfunction "1_1") (pintype "passive"))
      (node (ref "C107") (pin "1") (pinfunction "1_1") (pintype "passive"))
      (node (ref "C117") (pin "1") (pinfunction "1_1") (pintype "passive"))
      (node (ref "C118") (pin "1") (pinfunction "1_1") (pintype "passive"))
      (node (ref "C119") (pin "1") (pinfunction "1_1") (pintype "passive"))
      (node (ref "C121") (pin "2") (pinfunction "2_2") (pintype "passive"))
      (node (ref "C122") (pin "2") (pinfunction "2_2") (pintype "passive"))
      (node (ref "C123") (pin "2") (pinfunction "2_2") (pintype "passive"))
      (node (ref "C130") (pin "2") (pinfunction "2_2") (pintype "passive"))
      (node (ref "C131") (pin "2") (pinfunction "2_2") (pintype "passive"))
      (node (ref "C132") (pin "2") (pinfunction "2_2") (pintype "passive"))
      (node (ref "U20") (pin "1") (pinfunction "VDD_1") (pintype "passive"))
      (node (ref "U20") (pin "10") (pinfunction "VDD_10") (pintype "passive"))
      (node (ref "U20") (pin "11") (pinfunction "VDD_11") (pintype "passive"))
      (node (ref "U20") (pin "12") (pinfunction "VDD_12") (pintype "passive"))
      (node (ref "U20") (pin "13") (pinfunction "VDD_13") (pintype "passive"))
      (node (ref "U20") (pin "14") (pinfunction "VDD_14") (pintype "passive"))
      (node (ref "U20") (pin "15") (pinfunction "VDD_15") (pintype "passive"))
      (node (ref "U20") (pin "16") (pinfunction "VDD_16") (pintype "passive"))
      (node (ref "U20") (pin "17") (pinfunction "VDD_17") (pintype "passive"))
      (node (ref "U20") (pin "18") (pinfunction "VDD_18") (pintype "passive"))
      (node (ref "U20") (pin "19") (pinfunction "VDD_19") (pintype "passive"))
      (node (ref "U20") (pin "2") (pinfunction "VDD_2") (pintype "passive"))
      (node (ref "U20") (pin "20") (pinfunction "VDD_20") (pintype "passive"))
      (node (ref "U20") (pin "21") (pinfunction "VDD_21") (pintype "passive"))
      (node (ref "U20") (pin "24") (pinfunction "VDD_24") (pintype "passive"))
      (node (ref "U20") (pin "25") (pinfunction "VDD_25") (pintype "passive"))
      (node (ref "U20") (pin "26") (pinfunction "VDD_26") (pintype "passive"))
      (node (ref "U20") (pin "27") (pinfunction "VDD_27") (pintype "passive"))
      (node (ref "U20") (pin "28") (pinfunction "VDD_28") (pintype "passive"))
      (node (ref "U20") (pin "29") (pinfunction "VDD_29") (pintype "passive"))
      (node (ref "U20") (pin "3") (pinfunction "VDD_3") (pintype "passive"))
      (node (ref "U20") (pin "30") (pinfunction "VDD_30") (pintype "passive"))
      (node (ref "U20") (pin "31") (pinfunction "VDD_31") (pintype "passive"))
      (node (ref "U20") (pin "32") (pinfunction "VDD_32") (pintype "passive"))
      (node (ref "U20") (pin "33") (pinfunction "VDD_33") (pintype "passive"))
      (node (ref "U20") (pin "34") (pinfunction "VDD_34") (pintype "passive"))
      (node (ref "U20") (pin "35") (pinfunction "VDD_35") (pintype "passive"))
      (node (ref "U20") (pin "4") (pinfunction "VDD_4") (pintype "passive"))
      (node (ref "U20") (pin "5") (pinfunction "VDD_5") (pintype "passive"))
      (node (ref "U20") (pin "6") (pinfunction "VDD_6") (pintype "passive"))
      (node (ref "U20") (pin "7") (pinfunction "VDD_7") (pintype "passive"))
      (node (ref "U20") (pin "8") (pinfunction "VDD_8") (pintype "passive"))
      (node (ref "U20") (pin "9") (pinfunction "VDD_9") (pintype "passive"))
      (node (ref "U21") (pin "27") (pinfunction "V_7_27") (pintype "passive"))
      (node (ref "U22") (pin "36") (pinfunction "EP_36") (pintype "passive"))
    )
    (net (code "33") (name "/PWR9") (class "Default")
      (node (ref "C121") (pin "1") (pinfunction "1_1") (pintype "passive"))
      (node (ref "C122") (pin "1") (pinfunction "1_1") (pintype "passive"))
      (node (ref "C123") (pin "1") (pinfunction "1_1") (pintype "passive"))
      (node (ref "C124") (pin "2") (pinfunction "2_2") (pintype "passive"))
      (node (ref "C125") (pin "2") (pinfunction "2_2") (pintype "passive"))
      (node (ref "C126") (pin "2") (pinfunction "2_2") (pintype "passive"))
      (node (ref "C130") (pin "1") (pinfunction "1_1") (pintype "passive"))
      (node (ref "C131") (pin "1") (pinfunction "1_1") (pintype "passive"))
      (node (ref "C132") (pin "1") (pinfunction "1_1") (pintype "passive"))
      (node (ref "C133") (pin "2") (pinfunction "2_2") (pintype "passive"))
      (node (ref "C134") (pin "2") (pinfunction "2_2") (pintype "passive"))
      (node (ref "C135") (pin "2") (pinfunction "2_2") (pintype "passive"))
      (node (ref "U21") (pin "24") (pinfunction "V_8_24") (pintype "passive"))
      (node (ref "U22") (pin "1") (pinfunction "VDD_1") (pintype "passive"))
      (node (ref "U22") (pin "10") (pinfunction "VDD_10") (pintype "passive"))
      (node (ref "U22") (pin "11") (pinfunction "VDD_11") (pintype "passive"))
      (node (ref "U22") (pin "12") (pinfunction "VDD_12") (pintype "passive"))
      (node (ref "U22") (pin "13") (pinfunction "VDD_13") (pintype "passive"))
      (node (ref "U22") (pin "14") (pinfunction "VDD_14") (pintype "passive"))
      (node (ref "U22") (pin "15") (pinfunction "VDD_15") (pintype "passive"))
      (node (ref "U22") (pin "16") (pinfunction "VDD_16") (pintype "passive"))
      (node (ref "U22") (pin "17") (pinfunction "VDD_17") (pintype "passive"))
      (node (ref "U22") (pin "18") (pinfunction "VDD_18") (pintype "passive"))
      (node (ref "U22") (pin "19") (pinfunction "VDD_19") (pintype "passive"))
      (node (ref "U22") (pin "2") (pinfunction "VDD_2") (pintype "passive"))
      (node (ref "U22") (pin "20") (pinfunction "VDD_20") (pintype "passive"))
      (node (ref "U22") (pin "21") (pinfunction "VDD_21") (pintype "passive"))
      (node (ref "U22") (pin "24") (pinfunction "VDD_24") (pintype "passive"))
      (node (ref "U22") (pin "25") (pinfunction "VDD_25") (pintype "passive"))
      (node (ref "U22") (pin "26") (pinfunction "VDD_26") (pintype "passive"))
      (node (ref "U22") (pin "27") (pinfunction "VDD_27") (pintype "passive"))
      (node (ref "U22") (pin "28") (pinfunction "VDD_28") (pintype "passive"))
      (node (ref "U22") (pin "29") (pinfunction "VDD_29") (pintype "passive"))
      (node (ref "U22") (pin "3") (pinfunction "VDD_3") (pintype "passive"))
      (node (ref "U22") (pin "30") (pinfunction "VDD_30") (pintype "passive"))
      (node (ref "U22") (pin "31") (pinfunction "VDD_31") (pintype "passive"))
      (node (ref "U22") (pin "32") (pinfunction "VDD_32") (pintype "passive"))
      (node (ref "U22") (pin "33") (pinfunction "VDD_33") (pintype "passive"))
      (node (ref "U22") (pin "34") (pinfunction "VDD_34") (pintype "passive"))
      (node (ref "U22") (pin "35") (pinfunction "VDD_35") (pintype "passive"))
      (node (ref "U22") (pin "4") (pinfunction "VDD_4") (pintype "passive"))
      (node (ref "U22") (pin "5") (pinfunction "VDD_5") (pintype "passive"))
      (node (ref "U22") (pin "6") (pinfunction "VDD_6") (pintype "passive"))
      (node (ref "U22") (pin "7") (pinfunction "VDD_7") (pintype "passive"))
      (node (ref "U22") (pin "8") (pinfunction "VDD_8") (pintype "passive"))
      (node (ref "U22") (pin "9") (pinfunction "VDD_9") (pintype "passive"))
      (node (ref "U23") (pin "36") (pinfunction "EP_36") (pintype "passive"))
    )
    (net (code "34") (name "/PWR10") (class "Default")
      (node (ref "C124") (pin "1") (pinfunction "1_1") (pintype "passive"))
      (node (ref "C125") (pin "1") (pinfunction "1_1") (pintype "passive"))
      (node (ref "C126") (pin "1") (pinfunction "1_1") (pintype "passive"))
      (node (ref "C127") (pin "2") (pinfunction "2_2") (pintype "passive"))
      (node (ref "C128") (pin "2") (pinfunction "2_2") (pintype "passive"))
      (node (ref "C129") (pin "2") (pinfunction "2_2") (pintype "passive"))
      (node (ref "C133") (pin "1") (pinfunction "1_1") (pintype "passive"))
      (node (ref "C134") (pin "1") (pinfunction "1_1") (pintype "passive"))
      (node (ref "C135") (pin "1") (pinfunction "1_1") (pintype "passive"))
      (node (ref "C136") (pin "2") (pinfunction "2_2") (pintype "passive"))
      (node (ref "C137") (pin "2") (pinfunction "2_2") (pintype "passive"))
      (node (ref "C138") (pin "2") (pinfunction "2_2") (pintype "passive"))
      (node (ref "U21") (pin "21") (pinfunction "V_9_21") (pintype "passive"))
      (node (ref "U23") (pin "1") (pinfunction "VDD_1") (pintype "passive"))
      (node (ref "U23") (pin "10") (pinfunction "VDD_10") (pintype "passive"))
      (node (ref "U23") (pin "11") (pinfunction "VDD_11") (pintype "passive"))
      (node (ref "U23") (pin "12") (pinfunction "VDD_12") (pintype "passive"))
      (node (ref "U23") (pin "13") (pinfunction "VDD_13") (pintype "passive"))
      (node (ref "U23") (pin "14") (pinfunction "VDD_14") (pintype "passive"))
      (node (ref "U23") (pin "15") (pinfunction "VDD_15") (pintype "passive"))
      (node (ref "U23") (pin "16") (pinfunction "VDD_16") (pintype "passive"))
      (node (ref "U23") (pin "17") (pinfunction "VDD_17") (pintype "passive"))
      (node (ref "U23") (pin "18") (pinfunction "VDD_18") (pintype "passive"))
      (node (ref "U23") (pin "19") (pinfunction "VDD_19") (pintype "passive"))
      (node (ref "U23") (pin "2") (pinfunction "VDD_2") (pintype "passive"))
      (node (ref "U23") (pin "20") (pinfunction "VDD_20") (pintype "passive"))
      (node (ref "U23") (pin "21") (pinfunction "VDD_21") (pintype "passive"))
      (node (ref "U23") (pin "24") (pinfunction "VDD_24") (pintype "passive"))
      (node (ref "U23") (pin "25") (pinfunction "VDD_25") (pintype "passive"))
      (node (ref "U23") (pin "26") (pinfunction "VDD_26") (pintype "passive"))
      (node (ref "U23") (pin "27") (pinfunction "VDD_27") (pintype "passive"))
      (node (ref "U23") (pin "28") (pinfunction "VDD_28") (pintype "passive"))
      (node (ref "U23") (pin "29") (pinfunction "VDD_29") (pintype "passive"))
      (node (ref "U23") (pin "3") (pinfunction "VDD_3") (pintype "passive"))
      (node (ref "U23") (pin "30") (pinfunction "VDD_30") (pintype "passive"))
      (node (ref "U23") (pin "31") (pinfunction "VDD_31") (pintype "passive"))
      (node (ref "U23") (pin "32") (pinfunction "VDD_32") (pintype "passive"))
      (node (ref "U23") (pin "33") (pinfunction "VDD_33") (pintype "passive"))
      (node (ref "U23") (pin "34") (pinfunction "VDD_34") (pintype "passive"))
      (node (ref "U23") (pin "35") (pinfunction "VDD_35") (pintype "passive"))
      (node (ref "U23") (pin "4") (pinfunction "VDD_4") (pintype "passive"))
      (node (ref "U23") (pin "5") (pinfunction "VDD_5") (pintype "passive"))
      (node (ref "U23") (pin "6") (pinfunction "VDD_6") (pintype "passive"))
      (node (ref "U23") (pin "7") (pinfunction "VDD_7") (pintype "passive"))
      (node (ref "U23") (pin "8") (pinfunction "VDD_8") (pintype "passive"))
      (node (ref "U23") (pin "9") (pinfunction "VDD_9") (pintype "passive"))
      (node (ref "U24") (pin "36") (pinfunction "EP_36") (pintype "passive"))
    )
    (net (code "35") (name "/PWR11") (class "Default")
      (node (ref "C120") (pin "1") (pinfunction "1_1") (pintype "passive"))
      (node (ref "C127") (pin "1") (pinfunction "1_1") (pintype "passive"))
      (node (ref "C128") (pin "1") (pinfunction "1_1") (pintype "passive"))
      (node (ref "C129") (pin "1") (pinfunction "1_1") (pintype "passive"))
      (node (ref "C136") (pin "1") (pinfunction "1_1") (pintype "passive"))
      (node (ref "C137") (pin "1") (pinfunction "1_1") (pintype "passive"))
      (node (ref "C138") (pin "1") (pinfunction "1_1") (pintype "passive"))
      (node (ref "U21") (pin "17") (pinfunction "VDD_17") (pintype "passive"))
      (node (ref "U24") (pin "1") (pinfunction "VDD_1") (pintype "passive"))
      (node (ref "U24") (pin "10") (pinfunction "VDD_10") (pintype "passive"))
      (node (ref "U24") (pin "11") (pinfunction "VDD_11") (pintype "passive"))
      (node (ref "U24") (pin "12") (pinfunction "VDD_12") (pintype "passive"))
      (node (ref "U24") (pin "13") (pinfunction "VDD_13") (pintype "passive"))
      (node (ref "U24") (pin "14") (pinfunction "VDD_14") (pintype "passive"))
      (node (ref "U24") (pin "15") (pinfunction "VDD_15") (pintype "passive"))
      (node (ref "U24") (pin "16") (pinfunction "VDD_16") (pintype "passive"))
      (node (ref "U24") (pin "17") (pinfunction "VDD_17") (pintype "passive"))
      (node (ref "U24") (pin "18") (pinfunction "VDD_18") (pintype "passive"))
      (node (ref "U24") (pin "19") (pinfunction "VDD_19") (pintype "passive"))
      (node (ref "U24") (pin "2") (pinfunction "VDD_2") (pintype "passive"))
      (node (ref "U24") (pin "20") (pinfunction "VDD_20") (pintype "passive"))
      (node (ref "U24") (pin "21") (pinfunction "VDD_21") (pintype "passive"))
      (node (ref "U24") (pin "24") (pinfunction "VDD_24") (pintype "passive"))
      (node (ref "U24") (pin "25") (pinfunction "VDD_25") (pintype "passive"))
      (node (ref "U24") (pin "26") (pinfunction "VDD_26") (pintype "passive"))
      (node (ref "U24") (pin "27") (pinfunction "VDD_27") (pintype "passive"))
      (node (ref "U24") (pin "28") (pinfunction "VDD_28") (pintype "passive"))
      (node (ref "U24") (pin "29") (pinfunction "VDD_29") (pintype "passive"))
      (node (ref "U24") (pin "3") (pinfunction "VDD_3") (pintype "passive"))
      (node (ref "U24") (pin "30") (pinfunction "VDD_30") (pintype "passive"))
      (node (ref "U24") (pin "31") (pinfunction "VDD_31") (pintype "passive"))
      (node (ref "U24") (pin "32") (pinfunction "VDD_32") (pintype "passive"))
      (node (ref "U24") (pin "33") (pinfunction "VDD_33") (pintype "passive"))
      (node (ref "U24") (pin "34") (pinfunction "VDD_34") (pintype "passive"))
      (node (ref "U24") (pin "35") (pinfunction "VDD_35") (pintype "passive"))
      (node (ref "U24") (pin "4") (pinfunction "VDD_4") (pintype "passive"))
      (node (ref "U24") (pin "5") (pinfunction "VDD_5") (pintype "passive"))
      (node (ref "U24") (pin "6") (pinfunction "VDD_6") (pintype "passive"))
      (node (ref "U24") (pin "7") (pinfunction "VDD_7") (pintype "passive"))
      (node (ref "U24") (pin "8") (pinfunction "VDD_8") (pintype "passive"))
      (node (ref "U24") (pin "9") (pinfunction "VDD_9") (pintype "passive"))
    )
    (net (code "36") (name "/RX0_1") (class "Default")
      (node (ref "U21") (pin "12") (pinfunction "RX_0_12") (pintype "passive"))
    )
    (net (code "37") (name "/RX1_1") (class "Default")
      (node (ref "U21") (pin "14") (pinfunction "RX_1_14") (pintype "passive"))
    )
    (net (code "38") (name "/RX2_1") (class "Default")
      (node (ref "U21") (pin "16") (pinfunction "RX_2_16") (pintype "passive"))
    )
    (net (code "39") (name "/TX0_1") (class "Default")
      (node (ref "U21") (pin "11") (pinfunction "TX_0_11") (pintype "passive"))
    )
    (net (code "40") (name "/TX1_1") (class "Default")
      (node (ref "U21") (pin "13") (pinfunction "TX_1_13") (pintype "passive"))
    )
    (net (code "41") (name "/TX2_1") (class "Default")
      (node (ref "U21") (pin "15") (pinfunction "TX_2_15") (pintype "passive"))
    )
  )
)
